# 56_ch_sample-and-hold_card_v1_1.net
KiCad netlist of a schematic drawn in EAGLE
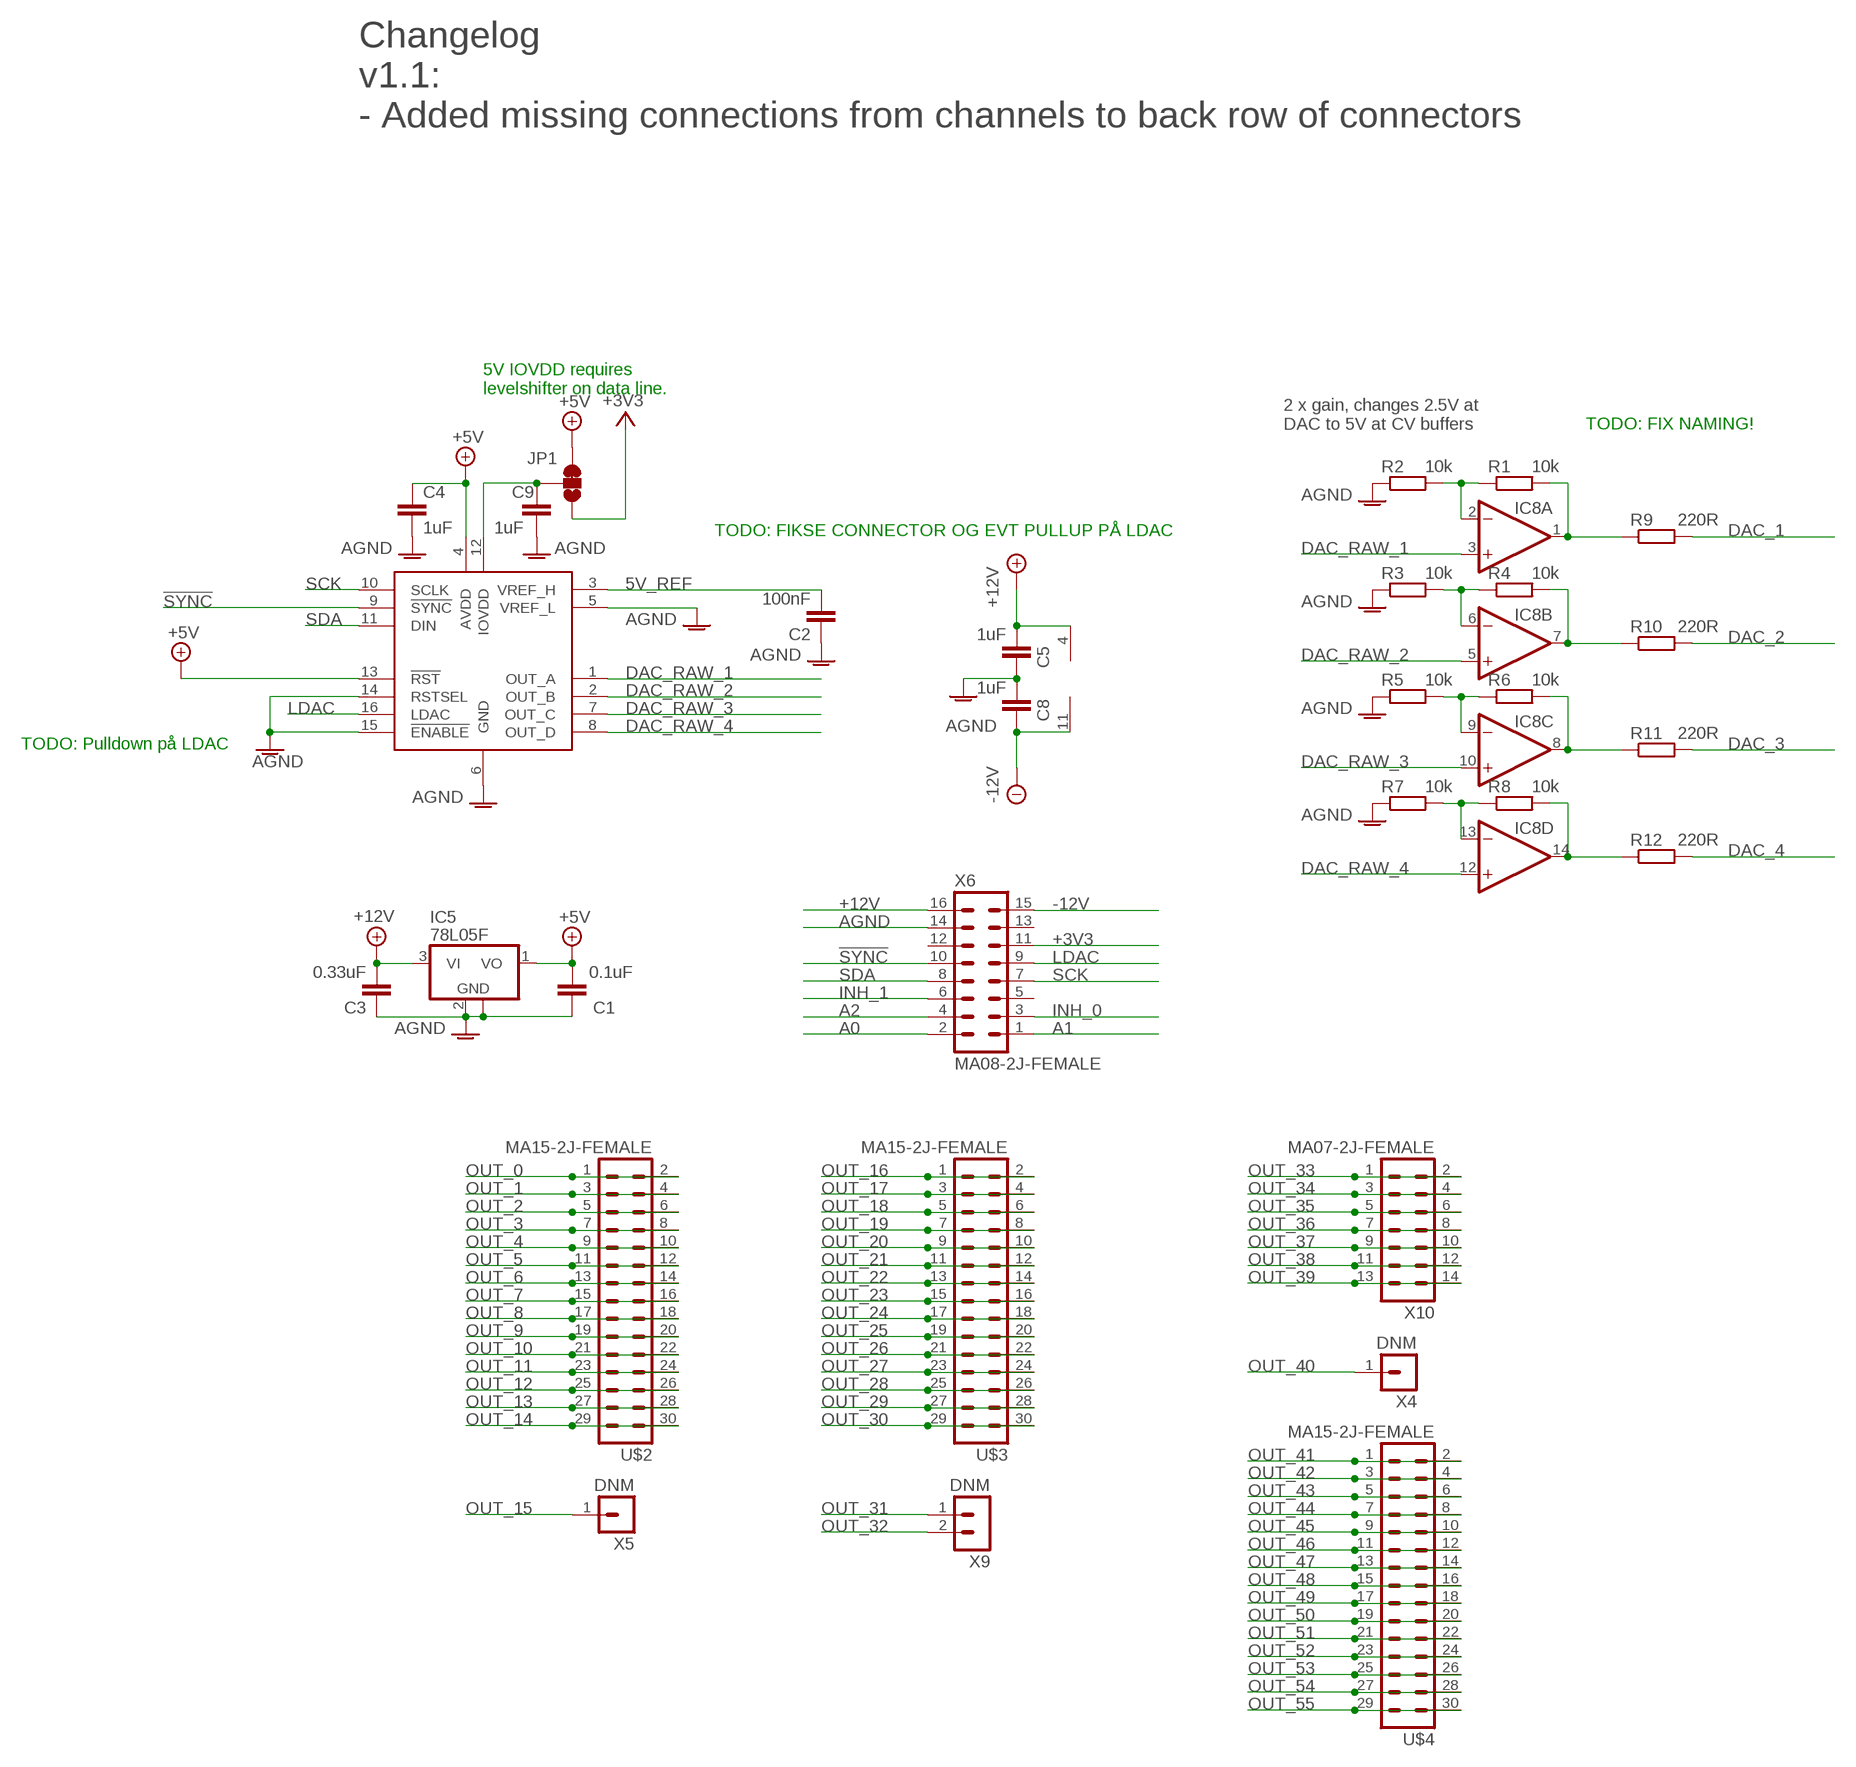
[diagram p0: schematic, sheet 1]
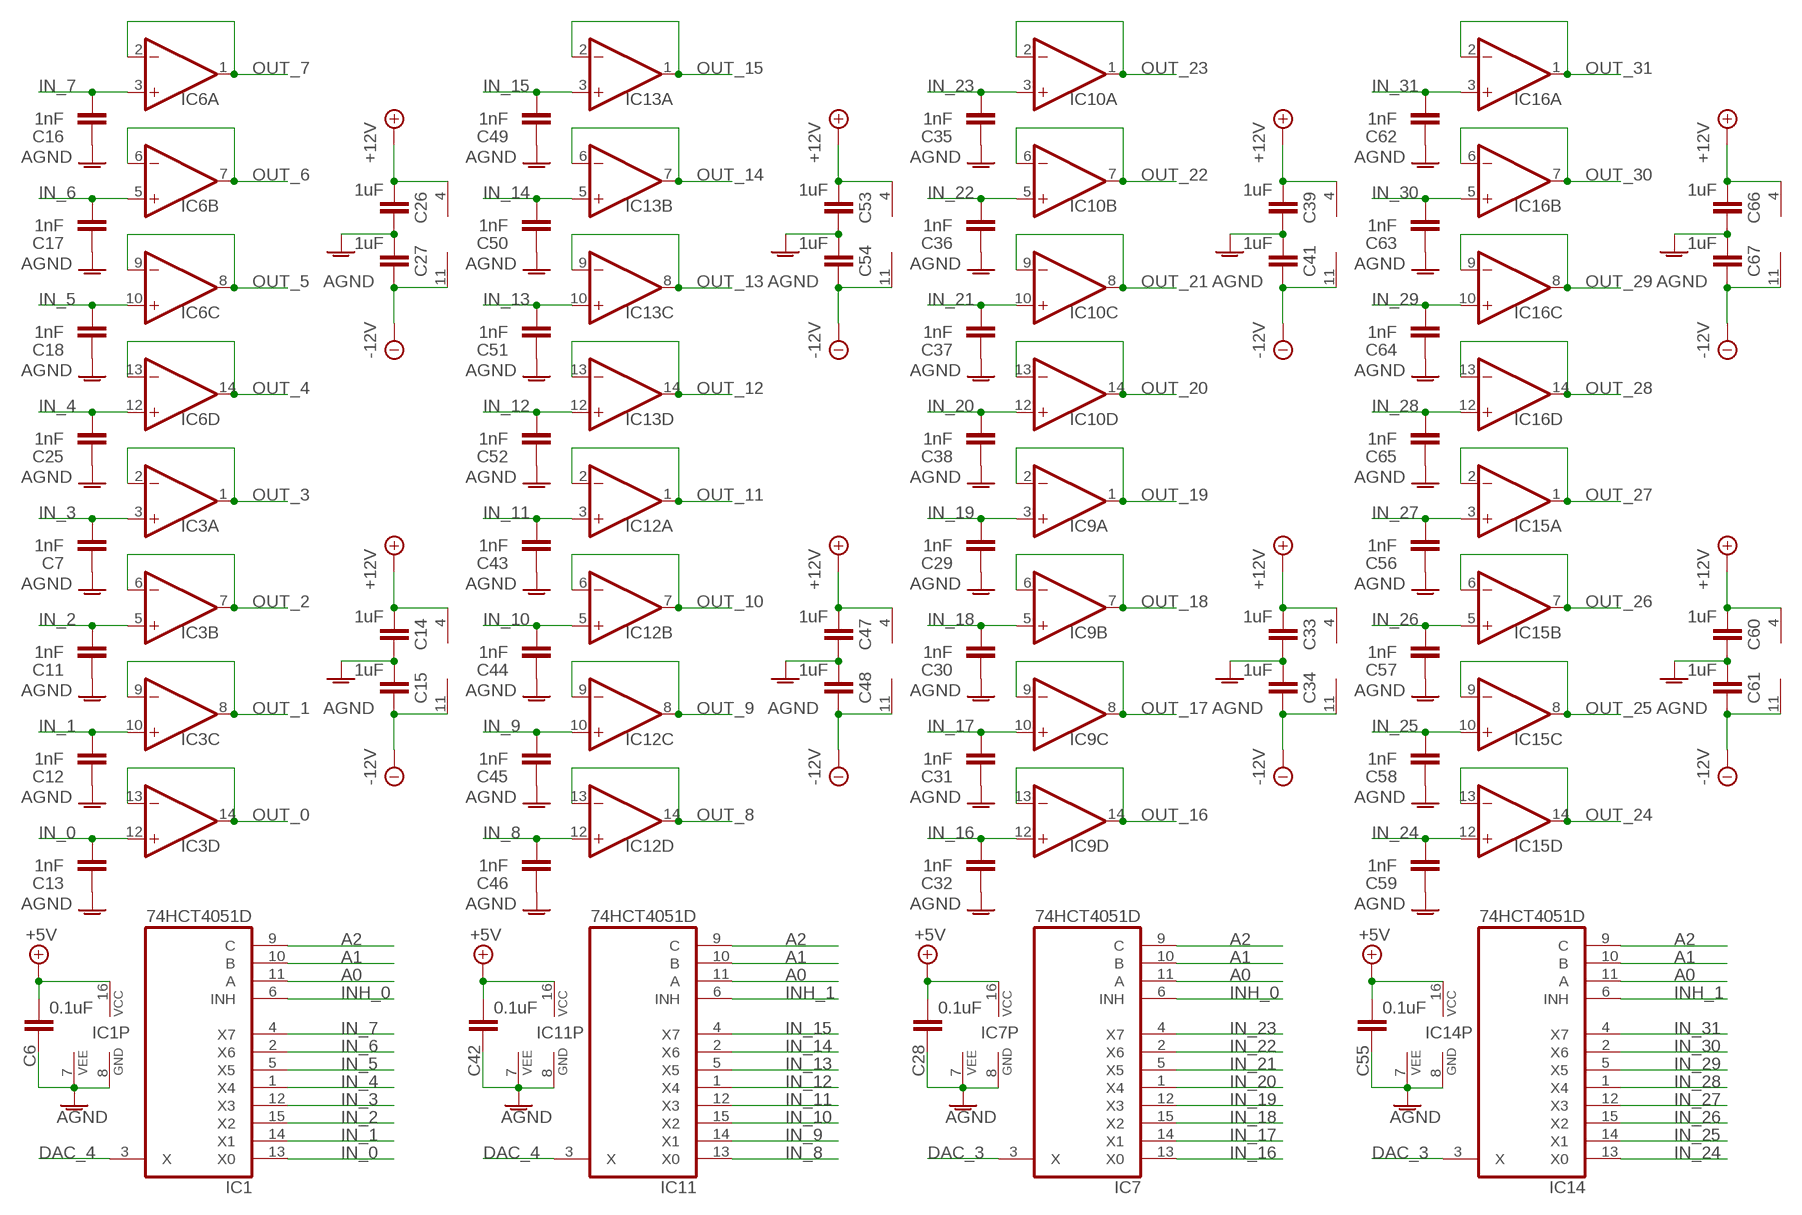
[diagram p1: schematic, sheet 2]
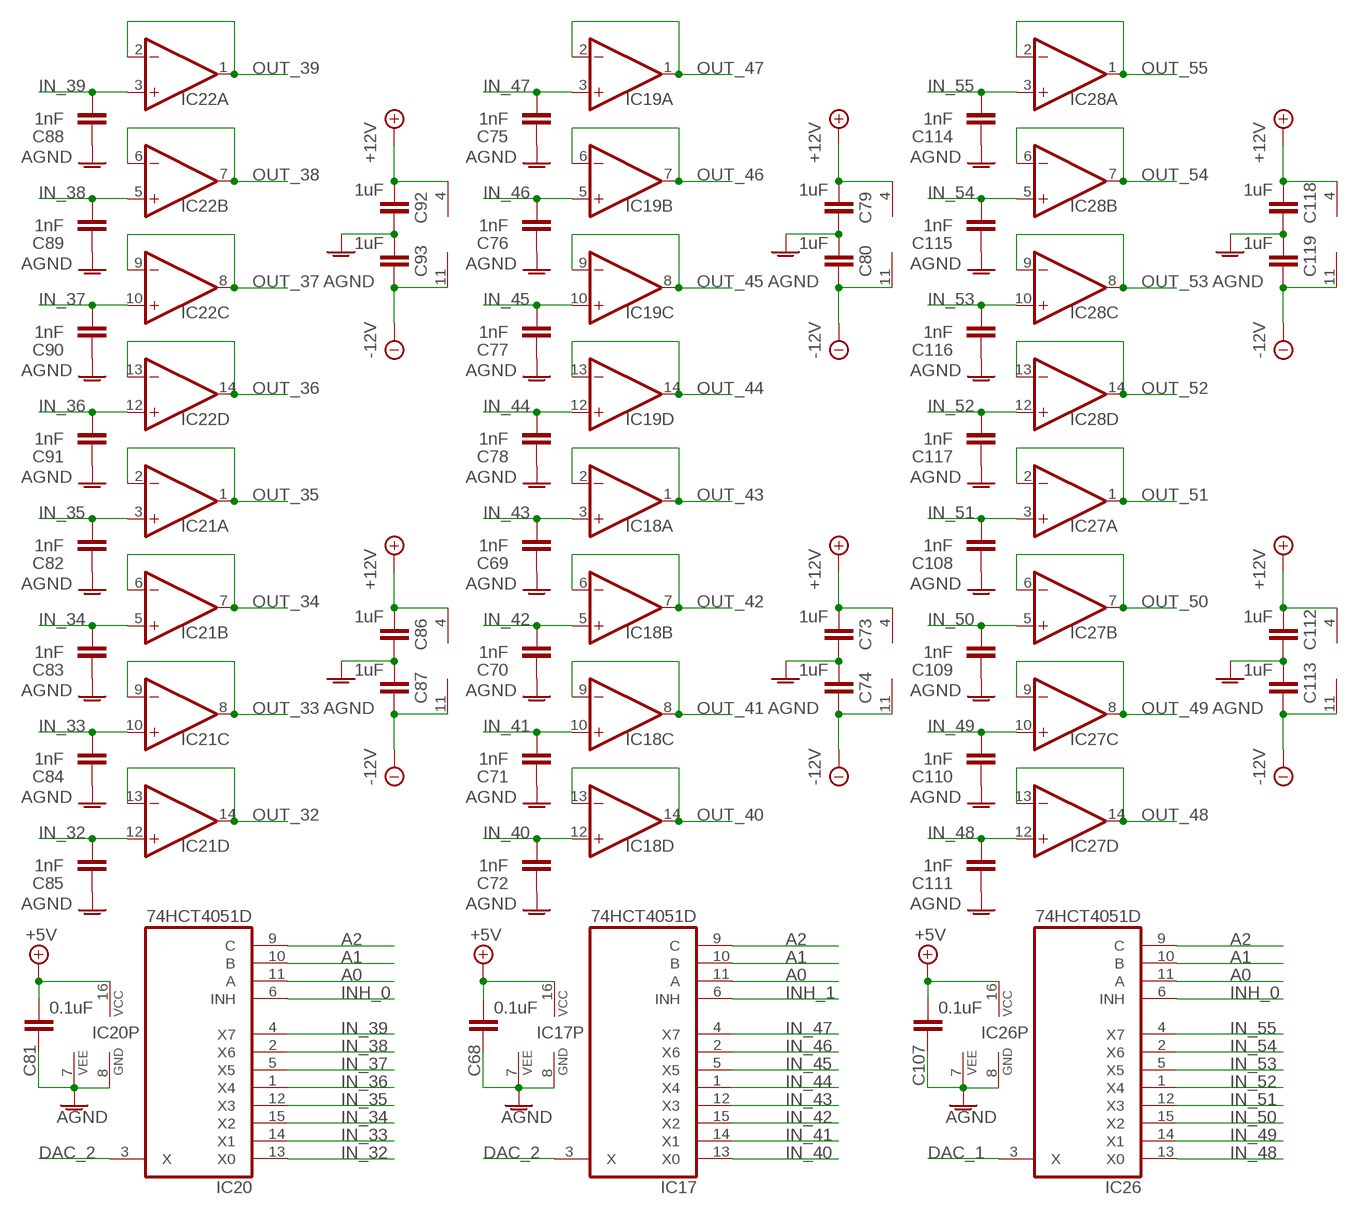
[diagram p2: schematic, sheet 3]

(export (version "E")
  (design (tool "Eeschema 10.0.6"))
  (components
    (comp (ref "C68")
      (value "0.1uF")
      (footprint "eagle-import:C0402-J")
      (libsource (lib "eagle-import") (part "C-EU-J0402"))
    )
    (comp (ref "C69")
      (value "1nF")
      (footprint "eagle-import:C0603-J")
      (libsource (lib "eagle-import") (part "C-EU-J0603"))
    )
    (comp (ref "C70")
      (value "1nF")
      (footprint "eagle-import:C0603-J")
      (libsource (lib "eagle-import") (part "C-EU-J0603"))
    )
    (comp (ref "C71")
      (value "1nF")
      (footprint "eagle-import:C0603-J")
      (libsource (lib "eagle-import") (part "C-EU-J0603"))
    )
    (comp (ref "C72")
      (value "1nF")
      (footprint "eagle-import:C0603-J")
      (libsource (lib "eagle-import") (part "C-EU-J0603"))
    )
    (comp (ref "C73")
      (value "1uF")
      (footprint "eagle-import:C0402-J")
      (libsource (lib "eagle-import") (part "C-EU-J0402"))
    )
    (comp (ref "C74")
      (value "1uF")
      (footprint "eagle-import:C0402-J")
      (libsource (lib "eagle-import") (part "C-EU-J0402"))
    )
    (comp (ref "C75")
      (value "1nF")
      (footprint "eagle-import:C0603-J")
      (libsource (lib "eagle-import") (part "C-EU-J0603"))
    )
    (comp (ref "C76")
      (value "1nF")
      (footprint "eagle-import:C0603-J")
      (libsource (lib "eagle-import") (part "C-EU-J0603"))
    )
    (comp (ref "C77")
      (value "1nF")
      (footprint "eagle-import:C0603-J")
      (libsource (lib "eagle-import") (part "C-EU-J0603"))
    )
    (comp (ref "C78")
      (value "1nF")
      (footprint "eagle-import:C0603-J")
      (libsource (lib "eagle-import") (part "C-EU-J0603"))
    )
    (comp (ref "C79")
      (value "1uF")
      (footprint "eagle-import:C0402-J")
      (libsource (lib "eagle-import") (part "C-EU-J0402"))
    )
    (comp (ref "C80")
      (value "1uF")
      (footprint "eagle-import:C0402-J")
      (libsource (lib "eagle-import") (part "C-EU-J0402"))
    )
    (comp (ref "C81")
      (value "0.1uF")
      (footprint "eagle-import:C0402-J")
      (libsource (lib "eagle-import") (part "C-EU-J0402"))
    )
    (comp (ref "C82")
      (value "1nF")
      (footprint "eagle-import:C0603-J")
      (libsource (lib "eagle-import") (part "C-EU-J0603"))
    )
    (comp (ref "C83")
      (value "1nF")
      (footprint "eagle-import:C0603-J")
      (libsource (lib "eagle-import") (part "C-EU-J0603"))
    )
    (comp (ref "C84")
      (value "1nF")
      (footprint "eagle-import:C0603-J")
      (libsource (lib "eagle-import") (part "C-EU-J0603"))
    )
    (comp (ref "C85")
      (value "1nF")
      (footprint "eagle-import:C0603-J")
      (libsource (lib "eagle-import") (part "C-EU-J0603"))
    )
    (comp (ref "C86")
      (value "1uF")
      (footprint "eagle-import:C0402-J")
      (libsource (lib "eagle-import") (part "C-EU-J0402"))
    )
    (comp (ref "C87")
      (value "1uF")
      (footprint "eagle-import:C0402-J")
      (libsource (lib "eagle-import") (part "C-EU-J0402"))
    )
    (comp (ref "C88")
      (value "1nF")
      (footprint "eagle-import:C0603-J")
      (libsource (lib "eagle-import") (part "C-EU-J0603"))
    )
    (comp (ref "C89")
      (value "1nF")
      (footprint "eagle-import:C0603-J")
      (libsource (lib "eagle-import") (part "C-EU-J0603"))
    )
    (comp (ref "C90")
      (value "1nF")
      (footprint "eagle-import:C0603-J")
      (libsource (lib "eagle-import") (part "C-EU-J0603"))
    )
    (comp (ref "C91")
      (value "1nF")
      (footprint "eagle-import:C0603-J")
      (libsource (lib "eagle-import") (part "C-EU-J0603"))
    )
    (comp (ref "C92")
      (value "1uF")
      (footprint "eagle-import:C0402-J")
      (libsource (lib "eagle-import") (part "C-EU-J0402"))
    )
    (comp (ref "C93")
      (value "1uF")
      (footprint "eagle-import:C0402-J")
      (libsource (lib "eagle-import") (part "C-EU-J0402"))
    )
    (comp (ref "C107")
      (value "0.1uF")
      (footprint "eagle-import:C0402-J")
      (libsource (lib "eagle-import") (part "C-EU-J0402"))
    )
    (comp (ref "C108")
      (value "1nF")
      (footprint "eagle-import:C0603-J")
      (libsource (lib "eagle-import") (part "C-EU-J0603"))
    )
    (comp (ref "C109")
      (value "1nF")
      (footprint "eagle-import:C0603-J")
      (libsource (lib "eagle-import") (part "C-EU-J0603"))
    )
    (comp (ref "C110")
      (value "1nF")
      (footprint "eagle-import:C0603-J")
      (libsource (lib "eagle-import") (part "C-EU-J0603"))
    )
    (comp (ref "C111")
      (value "1nF")
      (footprint "eagle-import:C0603-J")
      (libsource (lib "eagle-import") (part "C-EU-J0603"))
    )
    (comp (ref "C112")
      (value "1uF")
      (footprint "eagle-import:C0402-J")
      (libsource (lib "eagle-import") (part "C-EU-J0402"))
    )
    (comp (ref "C113")
      (value "1uF")
      (footprint "eagle-import:C0402-J")
      (libsource (lib "eagle-import") (part "C-EU-J0402"))
    )
    (comp (ref "C114")
      (value "1nF")
      (footprint "eagle-import:C0603-J")
      (libsource (lib "eagle-import") (part "C-EU-J0603"))
    )
    (comp (ref "C115")
      (value "1nF")
      (footprint "eagle-import:C0603-J")
      (libsource (lib "eagle-import") (part "C-EU-J0603"))
    )
    (comp (ref "C116")
      (value "1nF")
      (footprint "eagle-import:C0603-J")
      (libsource (lib "eagle-import") (part "C-EU-J0603"))
    )
    (comp (ref "C117")
      (value "1nF")
      (footprint "eagle-import:C0603-J")
      (libsource (lib "eagle-import") (part "C-EU-J0603"))
    )
    (comp (ref "C118")
      (value "1uF")
      (footprint "eagle-import:C0402-J")
      (libsource (lib "eagle-import") (part "C-EU-J0402"))
    )
    (comp (ref "C119")
      (value "1uF")
      (footprint "eagle-import:C0402-J")
      (libsource (lib "eagle-import") (part "C-EU-J0402"))
    )
    (comp (ref "IC17")
      (value "74HCT4051D")
      (footprint "eagle-import:SO16")
      (libsource (lib "eagle-import") (part "4051D"))
    )
    (comp (ref "IC18")
      (value "TL074JT")
      (footprint "eagle-import:TSSOP14J")
      (libsource (lib "eagle-import") (part "TL074JT"))
    )
    (comp (ref "IC19")
      (value "TL074JT")
      (footprint "eagle-import:TSSOP14J")
      (libsource (lib "eagle-import") (part "TL074JT"))
    )
    (comp (ref "IC20")
      (value "74HCT4051D")
      (footprint "eagle-import:SO16")
      (libsource (lib "eagle-import") (part "4051D"))
    )
    (comp (ref "IC21")
      (value "TL074JT")
      (footprint "eagle-import:TSSOP14J")
      (libsource (lib "eagle-import") (part "TL074JT"))
    )
    (comp (ref "IC22")
      (value "TL074JT")
      (footprint "eagle-import:TSSOP14J")
      (libsource (lib "eagle-import") (part "TL074JT"))
    )
    (comp (ref "IC26")
      (value "74HCT4051D")
      (footprint "eagle-import:SO16")
      (libsource (lib "eagle-import") (part "4051D"))
    )
    (comp (ref "IC27")
      (value "TL074JT")
      (footprint "eagle-import:TSSOP14J")
      (libsource (lib "eagle-import") (part "TL074JT"))
    )
    (comp (ref "IC28")
      (value "TL074JT")
      (footprint "eagle-import:TSSOP14J")
      (libsource (lib "eagle-import") (part "TL074JT"))
    )
    (comp (ref "C1")
      (value "0.1uF")
      (footprint "eagle-import:C0603")
      (libsource (lib "eagle-import") (part "C-EUC0603"))
    )
    (comp (ref "C2")
      (value "100nF")
      (footprint "eagle-import:C0603")
      (libsource (lib "eagle-import") (part "C-EUC0603"))
    )
    (comp (ref "C3")
      (value "0.33uF")
      (footprint "eagle-import:C0603")
      (libsource (lib "eagle-import") (part "C-EUC0603"))
    )
    (comp (ref "C4")
      (value "1uF")
      (footprint "eagle-import:C0402-J")
      (libsource (lib "eagle-import") (part "C-EU-J0402"))
    )
    (comp (ref "C5")
      (value "1uF")
      (footprint "eagle-import:C0402-J")
      (libsource (lib "eagle-import") (part "C-EU-J0402"))
    )
    (comp (ref "C8")
      (value "1uF")
      (footprint "eagle-import:C0402-J")
      (libsource (lib "eagle-import") (part "C-EU-J0402"))
    )
    (comp (ref "C9")
      (value "1uF")
      (footprint "eagle-import:C0402-J")
      (libsource (lib "eagle-import") (part "C-EU-J0402"))
    )
    (comp (ref "IC2")
      (value "DAC8565F")
      (footprint "eagle-import:DIL16-FM-CON")
      (libsource (lib "eagle-import") (part "DAC8565F"))
    )
    (comp (ref "IC5")
      (value "78L05F")
      (footprint "eagle-import:SOT89")
      (libsource (lib "eagle-import") (part "78LF05"))
    )
    (comp (ref "IC8")
      (value "TL074JT")
      (footprint "eagle-import:TSSOP14J")
      (libsource (lib "eagle-import") (part "TL074JT"))
    )
    (comp (ref "JP1")
      (value "JUMPER-SMT_3_1-NC_TRACE_NO-SILK_DNM")
      (footprint "eagle-import:SMT-JUMPER_3_1-NC_TRACE_NO-SILK")
      (libsource (lib "eagle-import") (part "JUMPER-SMT_3_1-NC_TRACE_NO-SILK"))
    )
    (comp (ref "R1")
      (value "10k")
      (footprint "eagle-import:R0603")
      (libsource (lib "eagle-import") (part "R-EU_R0603"))
    )
    (comp (ref "R2")
      (value "10k")
      (footprint "eagle-import:R0603")
      (libsource (lib "eagle-import") (part "R-EU_R0603"))
    )
    (comp (ref "R3")
      (value "10k")
      (footprint "eagle-import:R0603")
      (libsource (lib "eagle-import") (part "R-EU_R0603"))
    )
    (comp (ref "R4")
      (value "10k")
      (footprint "eagle-import:R0603")
      (libsource (lib "eagle-import") (part "R-EU_R0603"))
    )
    (comp (ref "R5")
      (value "10k")
      (footprint "eagle-import:R0603")
      (libsource (lib "eagle-import") (part "R-EU_R0603"))
    )
    (comp (ref "R6")
      (value "10k")
      (footprint "eagle-import:R0603")
      (libsource (lib "eagle-import") (part "R-EU_R0603"))
    )
    (comp (ref "R7")
      (value "10k")
      (footprint "eagle-import:R0603")
      (libsource (lib "eagle-import") (part "R-EU_R0603"))
    )
    (comp (ref "R8")
      (value "10k")
      (footprint "eagle-import:R0603")
      (libsource (lib "eagle-import") (part "R-EU_R0603"))
    )
    (comp (ref "R9")
      (value "220R")
      (footprint "eagle-import:R0603")
      (libsource (lib "eagle-import") (part "R-EU_R0603"))
    )
    (comp (ref "R10")
      (value "220R")
      (footprint "eagle-import:R0603")
      (libsource (lib "eagle-import") (part "R-EU_R0603"))
    )
    (comp (ref "R11")
      (value "220R")
      (footprint "eagle-import:R0603")
      (libsource (lib "eagle-import") (part "R-EU_R0603"))
    )
    (comp (ref "R12")
      (value "220R")
      (footprint "eagle-import:R0603")
      (libsource (lib "eagle-import") (part "R-EU_R0603"))
    )
    (comp (ref "U$2")
      (value "MA15-2J-FEMALE")
      (footprint "eagle-import:MA15-2J")
      (libsource (lib "eagle-import") (part "MA15-2J"))
    )
    (comp (ref "U$3")
      (value "MA15-2J-FEMALE")
      (footprint "eagle-import:MA15-2J")
      (libsource (lib "eagle-import") (part "MA15-2J"))
    )
    (comp (ref "U$4")
      (value "MA15-2J-FEMALE")
      (footprint "eagle-import:MA15-2J")
      (libsource (lib "eagle-import") (part "MA15-2J"))
    )
    (comp (ref "X4")
      (value "DNM")
      (footprint "eagle-import:MA01N-1J")
      (libsource (lib "eagle-import") (part "MA01-1JN"))
    )
    (comp (ref "X5")
      (value "DNM")
      (footprint "eagle-import:MA01N-1J")
      (libsource (lib "eagle-import") (part "MA01-1JN"))
    )
    (comp (ref "X6")
      (value "MA08-2J-FEMALE")
      (footprint "eagle-import:MA08-2J")
      (libsource (lib "eagle-import") (part "MA08-2J"))
    )
    (comp (ref "X9")
      (value "DNM")
      (footprint "eagle-import:MA02N-1J")
      (libsource (lib "eagle-import") (part "MA02-1JN"))
    )
    (comp (ref "X10")
      (value "MA07-2J-FEMALE")
      (footprint "eagle-import:MA07-2J")
      (libsource (lib "eagle-import") (part "MA07-2J"))
    )
    (comp (ref "C6")
      (value "0.1uF")
      (footprint "eagle-import:C0402-J")
      (libsource (lib "eagle-import") (part "C-EU-J0402"))
    )
    (comp (ref "C7")
      (value "1nF")
      (footprint "eagle-import:C0603-J")
      (libsource (lib "eagle-import") (part "C-EU-J0603"))
    )
    (comp (ref "C11")
      (value "1nF")
      (footprint "eagle-import:C0603-J")
      (libsource (lib "eagle-import") (part "C-EU-J0603"))
    )
    (comp (ref "C12")
      (value "1nF")
      (footprint "eagle-import:C0603-J")
      (libsource (lib "eagle-import") (part "C-EU-J0603"))
    )
    (comp (ref "C13")
      (value "1nF")
      (footprint "eagle-import:C0603-J")
      (libsource (lib "eagle-import") (part "C-EU-J0603"))
    )
    (comp (ref "C14")
      (value "1uF")
      (footprint "eagle-import:C0402-J")
      (libsource (lib "eagle-import") (part "C-EU-J0402"))
    )
    (comp (ref "C15")
      (value "1uF")
      (footprint "eagle-import:C0402-J")
      (libsource (lib "eagle-import") (part "C-EU-J0402"))
    )
    (comp (ref "C16")
      (value "1nF")
      (footprint "eagle-import:C0603-J")
      (libsource (lib "eagle-import") (part "C-EU-J0603"))
    )
    (comp (ref "C17")
      (value "1nF")
      (footprint "eagle-import:C0603-J")
      (libsource (lib "eagle-import") (part "C-EU-J0603"))
    )
    (comp (ref "C18")
      (value "1nF")
      (footprint "eagle-import:C0603-J")
      (libsource (lib "eagle-import") (part "C-EU-J0603"))
    )
    (comp (ref "C25")
      (value "1nF")
      (footprint "eagle-import:C0603-J")
      (libsource (lib "eagle-import") (part "C-EU-J0603"))
    )
    (comp (ref "C26")
      (value "1uF")
      (footprint "eagle-import:C0402-J")
      (libsource (lib "eagle-import") (part "C-EU-J0402"))
    )
    (comp (ref "C27")
      (value "1uF")
      (footprint "eagle-import:C0402-J")
      (libsource (lib "eagle-import") (part "C-EU-J0402"))
    )
    (comp (ref "C28")
      (value "0.1uF")
      (footprint "eagle-import:C0402-J")
      (libsource (lib "eagle-import") (part "C-EU-J0402"))
    )
    (comp (ref "C29")
      (value "1nF")
      (footprint "eagle-import:C0603-J")
      (libsource (lib "eagle-import") (part "C-EU-J0603"))
    )
    (comp (ref "C30")
      (value "1nF")
      (footprint "eagle-import:C0603-J")
      (libsource (lib "eagle-import") (part "C-EU-J0603"))
    )
    (comp (ref "C31")
      (value "1nF")
      (footprint "eagle-import:C0603-J")
      (libsource (lib "eagle-import") (part "C-EU-J0603"))
    )
    (comp (ref "C32")
      (value "1nF")
      (footprint "eagle-import:C0603-J")
      (libsource (lib "eagle-import") (part "C-EU-J0603"))
    )
    (comp (ref "C33")
      (value "1uF")
      (footprint "eagle-import:C0402-J")
      (libsource (lib "eagle-import") (part "C-EU-J0402"))
    )
    (comp (ref "C34")
      (value "1uF")
      (footprint "eagle-import:C0402-J")
      (libsource (lib "eagle-import") (part "C-EU-J0402"))
    )
    (comp (ref "C35")
      (value "1nF")
      (footprint "eagle-import:C0603-J")
      (libsource (lib "eagle-import") (part "C-EU-J0603"))
    )
    (comp (ref "C36")
      (value "1nF")
      (footprint "eagle-import:C0603-J")
      (libsource (lib "eagle-import") (part "C-EU-J0603"))
    )
    (comp (ref "C37")
      (value "1nF")
      (footprint "eagle-import:C0603-J")
      (libsource (lib "eagle-import") (part "C-EU-J0603"))
    )
    (comp (ref "C38")
      (value "1nF")
      (footprint "eagle-import:C0603-J")
      (libsource (lib "eagle-import") (part "C-EU-J0603"))
    )
    (comp (ref "C39")
      (value "1uF")
      (footprint "eagle-import:C0402-J")
      (libsource (lib "eagle-import") (part "C-EU-J0402"))
    )
    (comp (ref "C41")
      (value "1uF")
      (footprint "eagle-import:C0402-J")
      (libsource (lib "eagle-import") (part "C-EU-J0402"))
    )
    (comp (ref "C42")
      (value "0.1uF")
      (footprint "eagle-import:C0402-J")
      (libsource (lib "eagle-import") (part "C-EU-J0402"))
    )
    (comp (ref "C43")
      (value "1nF")
      (footprint "eagle-import:C0603-J")
      (libsource (lib "eagle-import") (part "C-EU-J0603"))
    )
    (comp (ref "C44")
      (value "1nF")
      (footprint "eagle-import:C0603-J")
      (libsource (lib "eagle-import") (part "C-EU-J0603"))
    )
    (comp (ref "C45")
      (value "1nF")
      (footprint "eagle-import:C0603-J")
      (libsource (lib "eagle-import") (part "C-EU-J0603"))
    )
    (comp (ref "C46")
      (value "1nF")
      (footprint "eagle-import:C0603-J")
      (libsource (lib "eagle-import") (part "C-EU-J0603"))
    )
    (comp (ref "C47")
      (value "1uF")
      (footprint "eagle-import:C0402-J")
      (libsource (lib "eagle-import") (part "C-EU-J0402"))
    )
    (comp (ref "C48")
      (value "1uF")
      (footprint "eagle-import:C0402-J")
      (libsource (lib "eagle-import") (part "C-EU-J0402"))
    )
    (comp (ref "C49")
      (value "1nF")
      (footprint "eagle-import:C0603-J")
      (libsource (lib "eagle-import") (part "C-EU-J0603"))
    )
    (comp (ref "C50")
      (value "1nF")
      (footprint "eagle-import:C0603-J")
      (libsource (lib "eagle-import") (part "C-EU-J0603"))
    )
    (comp (ref "C51")
      (value "1nF")
      (footprint "eagle-import:C0603-J")
      (libsource (lib "eagle-import") (part "C-EU-J0603"))
    )
    (comp (ref "C52")
      (value "1nF")
      (footprint "eagle-import:C0603-J")
      (libsource (lib "eagle-import") (part "C-EU-J0603"))
    )
    (comp (ref "C53")
      (value "1uF")
      (footprint "eagle-import:C0402-J")
      (libsource (lib "eagle-import") (part "C-EU-J0402"))
    )
    (comp (ref "C54")
      (value "1uF")
      (footprint "eagle-import:C0402-J")
      (libsource (lib "eagle-import") (part "C-EU-J0402"))
    )
    (comp (ref "C55")
      (value "0.1uF")
      (footprint "eagle-import:C0402-J")
      (libsource (lib "eagle-import") (part "C-EU-J0402"))
    )
    (comp (ref "C56")
      (value "1nF")
      (footprint "eagle-import:C0603-J")
      (libsource (lib "eagle-import") (part "C-EU-J0603"))
    )
    (comp (ref "C57")
      (value "1nF")
      (footprint "eagle-import:C0603-J")
      (libsource (lib "eagle-import") (part "C-EU-J0603"))
    )
    (comp (ref "C58")
      (value "1nF")
      (footprint "eagle-import:C0603-J")
      (libsource (lib "eagle-import") (part "C-EU-J0603"))
    )
    (comp (ref "C59")
      (value "1nF")
      (footprint "eagle-import:C0603-J")
      (libsource (lib "eagle-import") (part "C-EU-J0603"))
    )
    (comp (ref "C60")
      (value "1uF")
      (footprint "eagle-import:C0402-J")
      (libsource (lib "eagle-import") (part "C-EU-J0402"))
    )
    (comp (ref "C61")
      (value "1uF")
      (footprint "eagle-import:C0402-J")
      (libsource (lib "eagle-import") (part "C-EU-J0402"))
    )
    (comp (ref "C62")
      (value "1nF")
      (footprint "eagle-import:C0603-J")
      (libsource (lib "eagle-import") (part "C-EU-J0603"))
    )
    (comp (ref "C63")
      (value "1nF")
      (footprint "eagle-import:C0603-J")
      (libsource (lib "eagle-import") (part "C-EU-J0603"))
    )
    (comp (ref "C64")
      (value "1nF")
      (footprint "eagle-import:C0603-J")
      (libsource (lib "eagle-import") (part "C-EU-J0603"))
    )
    (comp (ref "C65")
      (value "1nF")
      (footprint "eagle-import:C0603-J")
      (libsource (lib "eagle-import") (part "C-EU-J0603"))
    )
    (comp (ref "C66")
      (value "1uF")
      (footprint "eagle-import:C0402-J")
      (libsource (lib "eagle-import") (part "C-EU-J0402"))
    )
    (comp (ref "C67")
      (value "1uF")
      (footprint "eagle-import:C0402-J")
      (libsource (lib "eagle-import") (part "C-EU-J0402"))
    )
    (comp (ref "IC1")
      (value "74HCT4051D")
      (footprint "eagle-import:SO16")
      (libsource (lib "eagle-import") (part "4051D"))
    )
    (comp (ref "IC3")
      (value "TL074JT")
      (footprint "eagle-import:TSSOP14J")
      (libsource (lib "eagle-import") (part "TL074JT"))
    )
    (comp (ref "IC6")
      (value "TL074JT")
      (footprint "eagle-import:TSSOP14J")
      (libsource (lib "eagle-import") (part "TL074JT"))
    )
    (comp (ref "IC7")
      (value "74HCT4051D")
      (footprint "eagle-import:SO16")
      (libsource (lib "eagle-import") (part "4051D"))
    )
    (comp (ref "IC9")
      (value "TL074JT")
      (footprint "eagle-import:TSSOP14J")
      (libsource (lib "eagle-import") (part "TL074JT"))
    )
    (comp (ref "IC10")
      (value "TL074JT")
      (footprint "eagle-import:TSSOP14J")
      (libsource (lib "eagle-import") (part "TL074JT"))
    )
    (comp (ref "IC11")
      (value "74HCT4051D")
      (footprint "eagle-import:SO16")
      (libsource (lib "eagle-import") (part "4051D"))
    )
    (comp (ref "IC12")
      (value "TL074JT")
      (footprint "eagle-import:TSSOP14J")
      (libsource (lib "eagle-import") (part "TL074JT"))
    )
    (comp (ref "IC13")
      (value "TL074JT")
      (footprint "eagle-import:TSSOP14J")
      (libsource (lib "eagle-import") (part "TL074JT"))
    )
    (comp (ref "IC14")
      (value "74HCT4051D")
      (footprint "eagle-import:SO16")
      (libsource (lib "eagle-import") (part "4051D"))
    )
    (comp (ref "IC15")
      (value "TL074JT")
      (footprint "eagle-import:TSSOP14J")
      (libsource (lib "eagle-import") (part "TL074JT"))
    )
    (comp (ref "IC16")
      (value "TL074JT")
      (footprint "eagle-import:TSSOP14J")
      (libsource (lib "eagle-import") (part "TL074JT"))
    )
  )
  (nets
    (net (code "1") (name "+3V3") (class "Default")
      (node (ref "JP1") (pin "1") (pinfunction "1_1") (pintype "passive"))
      (node (ref "X6") (pin "11") (pinfunction "11_11") (pintype "passive"))
    )
    (net (code "2") (name "+5V") (class "Default")
      (node (ref "C1") (pin "2") (pinfunction "2_2") (pintype "passive"))
      (node (ref "C107") (pin "2") (pinfunction "2_2") (pintype "passive"))
      (node (ref "C28") (pin "2") (pinfunction "2_2") (pintype "passive"))
      (node (ref "C4") (pin "1") (pinfunction "1_1") (pintype "passive"))
      (node (ref "C42") (pin "2") (pinfunction "2_2") (pintype "passive"))
      (node (ref "C55") (pin "2") (pinfunction "2_2") (pintype "passive"))
      (node (ref "C6") (pin "2") (pinfunction "2_2") (pintype "passive"))
      (node (ref "C68") (pin "2") (pinfunction "2_2") (pintype "passive"))
      (node (ref "C81") (pin "2") (pinfunction "2_2") (pintype "passive"))
      (node (ref "IC1") (pin "16") (pinfunction "VCC_16") (pintype "power_in"))
      (node (ref "IC11") (pin "16") (pinfunction "VCC_16") (pintype "power_in"))
      (node (ref "IC14") (pin "16") (pinfunction "VCC_16") (pintype "power_in"))
      (node (ref "IC17") (pin "16") (pinfunction "VCC_16") (pintype "power_in"))
      (node (ref "IC2") (pin "13") (pinfunction "~{RST}_13") (pintype "bidirectional"))
      (node (ref "IC2") (pin "4") (pinfunction "AVDD_4") (pintype "power_in"))
      (node (ref "IC20") (pin "16") (pinfunction "VCC_16") (pintype "power_in"))
      (node (ref "IC26") (pin "16") (pinfunction "VCC_16") (pintype "power_in"))
      (node (ref "IC5") (pin "1") (pinfunction "VO_1") (pintype "passive"))
      (node (ref "IC7") (pin "16") (pinfunction "VCC_16") (pintype "power_in"))
      (node (ref "JP1") (pin "3") (pinfunction "3_3") (pintype "passive"))
    )
    (net (code "3") (name "+12V") (class "Default")
      (node (ref "C112") (pin "1") (pinfunction "1_1") (pintype "passive"))
      (node (ref "C118") (pin "1") (pinfunction "1_1") (pintype "passive"))
      (node (ref "C14") (pin "1") (pinfunction "1_1") (pintype "passive"))
      (node (ref "C26") (pin "1") (pinfunction "1_1") (pintype "passive"))
      (node (ref "C3") (pin "2") (pinfunction "2_2") (pintype "passive"))
      (node (ref "C33") (pin "1") (pinfunction "1_1") (pintype "passive"))
      (node (ref "C39") (pin "1") (pinfunction "1_1") (pintype "passive"))
      (node (ref "C47") (pin "1") (pinfunction "1_1") (pintype "passive"))
      (node (ref "C5") (pin "1") (pinfunction "1_1") (pintype "passive"))
      (node (ref "C53") (pin "1") (pinfunction "1_1") (pintype "passive"))
      (node (ref "C60") (pin "1") (pinfunction "1_1") (pintype "passive"))
      (node (ref "C66") (pin "1") (pinfunction "1_1") (pintype "passive"))
      (node (ref "C73") (pin "1") (pinfunction "1_1") (pintype "passive"))
      (node (ref "C79") (pin "1") (pinfunction "1_1") (pintype "passive"))
      (node (ref "C86") (pin "1") (pinfunction "1_1") (pintype "passive"))
      (node (ref "C92") (pin "1") (pinfunction "1_1") (pintype "passive"))
      (node (ref "IC10") (pin "4") (pinfunction "V+_4") (pintype "power_in"))
      (node (ref "IC12") (pin "4") (pinfunction "V+_4") (pintype "power_in"))
      (node (ref "IC13") (pin "4") (pinfunction "V+_4") (pintype "power_in"))
      (node (ref "IC15") (pin "4") (pinfunction "V+_4") (pintype "power_in"))
      (node (ref "IC16") (pin "4") (pinfunction "V+_4") (pintype "power_in"))
      (node (ref "IC18") (pin "4") (pinfunction "V+_4") (pintype "power_in"))
      (node (ref "IC19") (pin "4") (pinfunction "V+_4") (pintype "power_in"))
      (node (ref "IC21") (pin "4") (pinfunction "V+_4") (pintype "power_in"))
      (node (ref "IC22") (pin "4") (pinfunction "V+_4") (pintype "power_in"))
      (node (ref "IC27") (pin "4") (pinfunction "V+_4") (pintype "power_in"))
      (node (ref "IC28") (pin "4") (pinfunction "V+_4") (pintype "power_in"))
      (node (ref "IC3") (pin "4") (pinfunction "V+_4") (pintype "power_in"))
      (node (ref "IC5") (pin "3") (pinfunction "VI_3") (pintype "input"))
      (node (ref "IC6") (pin "4") (pinfunction "V+_4") (pintype "power_in"))
      (node (ref "IC8") (pin "4") (pinfunction "V+_4") (pintype "power_in"))
      (node (ref "IC9") (pin "4") (pinfunction "V+_4") (pintype "power_in"))
      (node (ref "X6") (pin "16") (pinfunction "16_16") (pintype "passive"))
    )
    (net (code "4") (name "-12V") (class "Default")
      (node (ref "C113") (pin "2") (pinfunction "2_2") (pintype "passive"))
      (node (ref "C119") (pin "2") (pinfunction "2_2") (pintype "passive"))
      (node (ref "C15") (pin "2") (pinfunction "2_2") (pintype "passive"))
      (node (ref "C27") (pin "2") (pinfunction "2_2") (pintype "passive"))
      (node (ref "C34") (pin "2") (pinfunction "2_2") (pintype "passive"))
      (node (ref "C41") (pin "2") (pinfunction "2_2") (pintype "passive"))
      (node (ref "C48") (pin "2") (pinfunction "2_2") (pintype "passive"))
      (node (ref "C54") (pin "2") (pinfunction "2_2") (pintype "passive"))
      (node (ref "C61") (pin "2") (pinfunction "2_2") (pintype "passive"))
      (node (ref "C67") (pin "2") (pinfunction "2_2") (pintype "passive"))
      (node (ref "C74") (pin "2") (pinfunction "2_2") (pintype "passive"))
      (node (ref "C8") (pin "2") (pinfunction "2_2") (pintype "passive"))
      (node (ref "C80") (pin "2") (pinfunction "2_2") (pintype "passive"))
      (node (ref "C87") (pin "2") (pinfunction "2_2") (pintype "passive"))
      (node (ref "C93") (pin "2") (pinfunction "2_2") (pintype "passive"))
      (node (ref "IC10") (pin "11") (pinfunction "V-_11") (pintype "power_in"))
      (node (ref "IC12") (pin "11") (pinfunction "V-_11") (pintype "power_in"))
      (node (ref "IC13") (pin "11") (pinfunction "V-_11") (pintype "power_in"))
      (node (ref "IC15") (pin "11") (pinfunction "V-_11") (pintype "power_in"))
      (node (ref "IC16") (pin "11") (pinfunction "V-_11") (pintype "power_in"))
      (node (ref "IC18") (pin "11") (pinfunction "V-_11") (pintype "power_in"))
      (node (ref "IC19") (pin "11") (pinfunction "V-_11") (pintype "power_in"))
      (node (ref "IC21") (pin "11") (pinfunction "V-_11") (pintype "power_in"))
      (node (ref "IC22") (pin "11") (pinfunction "V-_11") (pintype "power_in"))
      (node (ref "IC27") (pin "11") (pinfunction "V-_11") (pintype "power_in"))
      (node (ref "IC28") (pin "11") (pinfunction "V-_11") (pintype "power_in"))
      (node (ref "IC3") (pin "11") (pinfunction "V-_11") (pintype "power_in"))
      (node (ref "IC6") (pin "11") (pinfunction "V-_11") (pintype "power_in"))
      (node (ref "IC8") (pin "11") (pinfunction "V-_11") (pintype "power_in"))
      (node (ref "IC9") (pin "11") (pinfunction "V-_11") (pintype "power_in"))
      (node (ref "X6") (pin "15") (pinfunction "15_15") (pintype "passive"))
    )
    (net (code "5") (name "5V_REF") (class "Default")
      (node (ref "C2") (pin "2") (pinfunction "2_2") (pintype "passive"))
      (node (ref "IC2") (pin "3") (pinfunction "VREF_H_3") (pintype "bidirectional"))
    )
    (net (code "6") (name "A0") (class "Default")
      (node (ref "IC1") (pin "11") (pinfunction "A_11") (pintype "input"))
      (node (ref "IC11") (pin "11") (pinfunction "A_11") (pintype "input"))
      (node (ref "IC14") (pin "11") (pinfunction "A_11") (pintype "input"))
      (node (ref "IC17") (pin "11") (pinfunction "A_11") (pintype "input"))
      (node (ref "IC20") (pin "11") (pinfunction "A_11") (pintype "input"))
      (node (ref "IC26") (pin "11") (pinfunction "A_11") (pintype "input"))
      (node (ref "IC7") (pin "11") (pinfunction "A_11") (pintype "input"))
      (node (ref "X6") (pin "2") (pinfunction "2_2") (pintype "passive"))
    )
    (net (code "7") (name "A1") (class "Default")
      (node (ref "IC1") (pin "10") (pinfunction "B_10") (pintype "input"))
      (node (ref "IC11") (pin "10") (pinfunction "B_10") (pintype "input"))
      (node (ref "IC14") (pin "10") (pinfunction "B_10") (pintype "input"))
      (node (ref "IC17") (pin "10") (pinfunction "B_10") (pintype "input"))
      (node (ref "IC20") (pin "10") (pinfunction "B_10") (pintype "input"))
      (node (ref "IC26") (pin "10") (pinfunction "B_10") (pintype "input"))
      (node (ref "IC7") (pin "10") (pinfunction "B_10") (pintype "input"))
      (node (ref "X6") (pin "1") (pinfunction "1_1") (pintype "passive"))
    )
    (net (code "8") (name "A2") (class "Default")
      (node (ref "IC1") (pin "9") (pinfunction "C_9") (pintype "input"))
      (node (ref "IC11") (pin "9") (pinfunction "C_9") (pintype "input"))
      (node (ref "IC14") (pin "9") (pinfunction "C_9") (pintype "input"))
      (node (ref "IC17") (pin "9") (pinfunction "C_9") (pintype "input"))
      (node (ref "IC20") (pin "9") (pinfunction "C_9") (pintype "input"))
      (node (ref "IC26") (pin "9") (pinfunction "C_9") (pintype "input"))
      (node (ref "IC7") (pin "9") (pinfunction "C_9") (pintype "input"))
      (node (ref "X6") (pin "4") (pinfunction "4_4") (pintype "passive"))
    )
    (net (code "9") (name "AGND") (class "Default")
      (node (ref "C1") (pin "1") (pinfunction "1_1") (pintype "passive"))
      (node (ref "C107") (pin "1") (pinfunction "1_1") (pintype "passive"))
      (node (ref "C108") (pin "1") (pinfunction "1_1") (pintype "passive"))
      (node (ref "C109") (pin "1") (pinfunction "1_1") (pintype "passive"))
      (node (ref "C11") (pin "1") (pinfunction "1_1") (pintype "passive"))
      (node (ref "C110") (pin "1") (pinfunction "1_1") (pintype "passive"))
      (node (ref "C111") (pin "1") (pinfunction "1_1") (pintype "passive"))
      (node (ref "C112") (pin "2") (pinfunction "2_2") (pintype "passive"))
      (node (ref "C113") (pin "1") (pinfunction "1_1") (pintype "passive"))
      (node (ref "C114") (pin "1") (pinfunction "1_1") (pintype "passive"))
      (node (ref "C115") (pin "1") (pinfunction "1_1") (pintype "passive"))
      (node (ref "C116") (pin "1") (pinfunction "1_1") (pintype "passive"))
      (node (ref "C117") (pin "1") (pinfunction "1_1") (pintype "passive"))
      (node (ref "C118") (pin "2") (pinfunction "2_2") (pintype "passive"))
      (node (ref "C119") (pin "1") (pinfunction "1_1") (pintype "passive"))
      (node (ref "C12") (pin "1") (pinfunction "1_1") (pintype "passive"))
      (node (ref "C13") (pin "1") (pinfunction "1_1") (pintype "passive"))
      (node (ref "C14") (pin "2") (pinfunction "2_2") (pintype "passive"))
      (node (ref "C15") (pin "1") (pinfunction "1_1") (pintype "passive"))
      (node (ref "C16") (pin "1") (pinfunction "1_1") (pintype "passive"))
      (node (ref "C17") (pin "1") (pinfunction "1_1") (pintype "passive"))
      (node (ref "C18") (pin "1") (pinfunction "1_1") (pintype "passive"))
      (node (ref "C2") (pin "1") (pinfunction "1_1") (pintype "passive"))
      (node (ref "C25") (pin "1") (pinfunction "1_1") (pintype "passive"))
      (node (ref "C26") (pin "2") (pinfunction "2_2") (pintype "passive"))
      (node (ref "C27") (pin "1") (pinfunction "1_1") (pintype "passive"))
      (node (ref "C28") (pin "1") (pinfunction "1_1") (pintype "passive"))
      (node (ref "C29") (pin "1") (pinfunction "1_1") (pintype "passive"))
      (node (ref "C3") (pin "1") (pinfunction "1_1") (pintype "passive"))
      (node (ref "C30") (pin "1") (pinfunction "1_1") (pintype "passive"))
      (node (ref "C31") (pin "1") (pinfunction "1_1") (pintype "passive"))
      (node (ref "C32") (pin "1") (pinfunction "1_1") (pintype "passive"))
      (node (ref "C33") (pin "2") (pinfunction "2_2") (pintype "passive"))
      (node (ref "C34") (pin "1") (pinfunction "1_1") (pintype "passive"))
      (node (ref "C35") (pin "1") (pinfunction "1_1") (pintype "passive"))
      (node (ref "C36") (pin "1") (pinfunction "1_1") (pintype "passive"))
      (node (ref "C37") (pin "1") (pinfunction "1_1") (pintype "passive"))
      (node (ref "C38") (pin "1") (pinfunction "1_1") (pintype "passive"))
      (node (ref "C39") (pin "2") (pinfunction "2_2") (pintype "passive"))
      (node (ref "C4") (pin "2") (pinfunction "2_2") (pintype "passive"))
      (node (ref "C41") (pin "1") (pinfunction "1_1") (pintype "passive"))
      (node (ref "C42") (pin "1") (pinfunction "1_1") (pintype "passive"))
      (node (ref "C43") (pin "1") (pinfunction "1_1") (pintype "passive"))
      (node (ref "C44") (pin "1") (pinfunction "1_1") (pintype "passive"))
      (node (ref "C45") (pin "1") (pinfunction "1_1") (pintype "passive"))
      (node (ref "C46") (pin "1") (pinfunction "1_1") (pintype "passive"))
      (node (ref "C47") (pin "2") (pinfunction "2_2") (pintype "passive"))
      (node (ref "C48") (pin "1") (pinfunction "1_1") (pintype "passive"))
      (node (ref "C49") (pin "1") (pinfunction "1_1") (pintype "passive"))
      (node (ref "C5") (pin "2") (pinfunction "2_2") (pintype "passive"))
      (node (ref "C50") (pin "1") (pinfunction "1_1") (pintype "passive"))
      (node (ref "C51") (pin "1") (pinfunction "1_1") (pintype "passive"))
      (node (ref "C52") (pin "1") (pinfunction "1_1") (pintype "passive"))
      (node (ref "C53") (pin "2") (pinfunction "2_2") (pintype "passive"))
      (node (ref "C54") (pin "1") (pinfunction "1_1") (pintype "passive"))
      (node (ref "C55") (pin "1") (pinfunction "1_1") (pintype "passive"))
      (node (ref "C56") (pin "1") (pinfunction "1_1") (pintype "passive"))
      (node (ref "C57") (pin "1") (pinfunction "1_1") (pintype "passive"))
      (node (ref "C58") (pin "1") (pinfunction "1_1") (pintype "passive"))
      (node (ref "C59") (pin "1") (pinfunction "1_1") (pintype "passive"))
      (node (ref "C6") (pin "1") (pinfunction "1_1") (pintype "passive"))
      (node (ref "C60") (pin "2") (pinfunction "2_2") (pintype "passive"))
      (node (ref "C61") (pin "1") (pinfunction "1_1") (pintype "passive"))
      (node (ref "C62") (pin "1") (pinfunction "1_1") (pintype "passive"))
      (node (ref "C63") (pin "1") (pinfunction "1_1") (pintype "passive"))
      (node (ref "C64") (pin "1") (pinfunction "1_1") (pintype "passive"))
      (node (ref "C65") (pin "1") (pinfunction "1_1") (pintype "passive"))
      (node (ref "C66") (pin "2") (pinfunction "2_2") (pintype "passive"))
      (node (ref "C67") (pin "1") (pinfunction "1_1") (pintype "passive"))
      (node (ref "C68") (pin "1") (pinfunction "1_1") (pintype "passive"))
      (node (ref "C69") (pin "1") (pinfunction "1_1") (pintype "passive"))
      (node (ref "C7") (pin "1") (pinfunction "1_1") (pintype "passive"))
      (node (ref "C70") (pin "1") (pinfunction "1_1") (pintype "passive"))
      (node (ref "C71") (pin "1") (pinfunction "1_1") (pintype "passive"))
      (node (ref "C72") (pin "1") (pinfunction "1_1") (pintype "passive"))
      (node (ref "C73") (pin "2") (pinfunction "2_2") (pintype "passive"))
      (node (ref "C74") (pin "1") (pinfunction "1_1") (pintype "passive"))
      (node (ref "C75") (pin "1") (pinfunction "1_1") (pintype "passive"))
      (node (ref "C76") (pin "1") (pinfunction "1_1") (pintype "passive"))
      (node (ref "C77") (pin "1") (pinfunction "1_1") (pintype "passive"))
      (node (ref "C78") (pin "1") (pinfunction "1_1") (pintype "passive"))
      (node (ref "C79") (pin "2") (pinfunction "2_2") (pintype "passive"))
      (node (ref "C8") (pin "1") (pinfunction "1_1") (pintype "passive"))
      (node (ref "C80") (pin "1") (pinfunction "1_1") (pintype "passive"))
      (node (ref "C81") (pin "1") (pinfunction "1_1") (pintype "passive"))
      (node (ref "C82") (pin "1") (pinfunction "1_1") (pintype "passive"))
      (node (ref "C83") (pin "1") (pinfunction "1_1") (pintype "passive"))
      (node (ref "C84") (pin "1") (pinfunction "1_1") (pintype "passive"))
      (node (ref "C85") (pin "1") (pinfunction "1_1") (pintype "passive"))
      (node (ref "C86") (pin "2") (pinfunction "2_2") (pintype "passive"))
      (node (ref "C87") (pin "1") (pinfunction "1_1") (pintype "passive"))
      (node (ref "C88") (pin "1") (pinfunction "1_1") (pintype "passive"))
      (node (ref "C89") (pin "1") (pinfunction "1_1") (pintype "passive"))
      (node (ref "C9") (pin "2") (pinfunction "2_2") (pintype "passive"))
      (node (ref "C90") (pin "1") (pinfunction "1_1") (pintype "passive"))
      (node (ref "C91") (pin "1") (pinfunction "1_1") (pintype "passive"))
      (node (ref "C92") (pin "2") (pinfunction "2_2") (pintype "passive"))
      (node (ref "C93") (pin "1") (pinfunction "1_1") (pintype "passive"))
      (node (ref "IC1") (pin "7") (pinfunction "VEE_7") (pintype "power_in"))
      (node (ref "IC1") (pin "8") (pinfunction "GND_8") (pintype "power_in"))
      (node (ref "IC11") (pin "7") (pinfunction "VEE_7") (pintype "power_in"))
      (node (ref "IC11") (pin "8") (pinfunction "GND_8") (pintype "power_in"))
      (node (ref "IC14") (pin "7") (pinfunction "VEE_7") (pintype "power_in"))
      (node (ref "IC14") (pin "8") (pinfunction "GND_8") (pintype "power_in"))
      (node (ref "IC17") (pin "7") (pinfunction "VEE_7") (pintype "power_in"))
      (node (ref "IC17") (pin "8") (pinfunction "GND_8") (pintype "power_in"))
      (node (ref "IC2") (pin "14") (pinfunction "RSTSEL_14") (pintype "bidirectional"))
      (node (ref "IC2") (pin "15") (pinfunction "~{ENABLE}_15") (pintype "bidirectional"))
      (node (ref "IC2") (pin "5") (pinfunction "VREF_L_5") (pintype "bidirectional"))
      (node (ref "IC2") (pin "6") (pinfunction "GND_6") (pintype "bidirectional"))
      (node (ref "IC20") (pin "7") (pinfunction "VEE_7") (pintype "power_in"))
      (node (ref "IC20") (pin "8") (pinfunction "GND_8") (pintype "power_in"))
      (node (ref "IC26") (pin "7") (pinfunction "VEE_7") (pintype "power_in"))
      (node (ref "IC26") (pin "8") (pinfunction "GND_8") (pintype "power_in"))
      (node (ref "IC5") (pin "2") (pinfunction "GND_2") (pintype "passive"))
      (node (ref "IC5") (pin "2@1") (pinfunction "GND_2@1") (pintype "passive"))
      (node (ref "IC7") (pin "7") (pinfunction "VEE_7") (pintype "power_in"))
      (node (ref "IC7") (pin "8") (pinfunction "GND_8") (pintype "power_in"))
      (node (ref "R2") (pin "1") (pinfunction "1_1") (pintype "passive"))
      (node (ref "R3") (pin "1") (pinfunction "1_1") (pintype "passive"))
      (node (ref "R5") (pin "1") (pinfunction "1_1") (pintype "passive"))
      (node (ref "R7") (pin "1") (pinfunction "1_1") (pintype "passive"))
      (node (ref "X6") (pin "14") (pinfunction "14_14") (pintype "passive"))
    )
    (net (code "10") (name "DAC_1") (class "Default")
      (node (ref "IC26") (pin "3") (pinfunction "X_3") (pintype "bidirectional"))
      (node (ref "R9") (pin "2") (pinfunction "2_2") (pintype "passive"))
    )
    (net (code "11") (name "DAC_2") (class "Default")
      (node (ref "IC17") (pin "3") (pinfunction "X_3") (pintype "bidirectional"))
      (node (ref "IC20") (pin "3") (pinfunction "X_3") (pintype "bidirectional"))
      (node (ref "R10") (pin "2") (pinfunction "2_2") (pintype "passive"))
    )
    (net (code "12") (name "DAC_3") (class "Default")
      (node (ref "IC14") (pin "3") (pinfunction "X_3") (pintype "bidirectional"))
      (node (ref "IC7") (pin "3") (pinfunction "X_3") (pintype "bidirectional"))
      (node (ref "R11") (pin "2") (pinfunction "2_2") (pintype "passive"))
    )
    (net (code "13") (name "DAC_4") (class "Default")
      (node (ref "IC1") (pin "3") (pinfunction "X_3") (pintype "bidirectional"))
      (node (ref "IC11") (pin "3") (pinfunction "X_3") (pintype "bidirectional"))
      (node (ref "R12") (pin "2") (pinfunction "2_2") (pintype "passive"))
    )
    (net (code "14") (name "DAC_RAW_1") (class "Default")
      (node (ref "IC2") (pin "1") (pinfunction "OUT_A_1") (pintype "bidirectional"))
      (node (ref "IC8") (pin "3") (pinfunction "+IN_3") (pintype "input"))
    )
    (net (code "15") (name "DAC_RAW_2") (class "Default")
      (node (ref "IC2") (pin "2") (pinfunction "OUT_B_2") (pintype "bidirectional"))
      (node (ref "IC8") (pin "5") (pinfunction "+IN_5") (pintype "input"))
    )
    (net (code "16") (name "DAC_RAW_3") (class "Default")
      (node (ref "IC2") (pin "7") (pinfunction "OUT_C_7") (pintype "bidirectional"))
      (node (ref "IC8") (pin "10") (pinfunction "+IN_10") (pintype "input"))
    )
    (net (code "17") (name "DAC_RAW_4") (class "Default")
      (node (ref "IC2") (pin "8") (pinfunction "OUT_D_8") (pintype "bidirectional"))
      (node (ref "IC8") (pin "12") (pinfunction "+IN_12") (pintype "input"))
    )
    (net (code "18") (name "INH_0") (class "Default")
      (node (ref "IC1") (pin "6") (pinfunction "INH_6") (pintype "input"))
      (node (ref "IC20") (pin "6") (pinfunction "INH_6") (pintype "input"))
      (node (ref "IC26") (pin "6") (pinfunction "INH_6") (pintype "input"))
      (node (ref "IC7") (pin "6") (pinfunction "INH_6") (pintype "input"))
      (node (ref "X6") (pin "3") (pinfunction "3_3") (pintype "passive"))
    )
    (net (code "19") (name "INH_1") (class "Default")
      (node (ref "IC11") (pin "6") (pinfunction "INH_6") (pintype "input"))
      (node (ref "IC14") (pin "6") (pinfunction "INH_6") (pintype "input"))
      (node (ref "IC17") (pin "6") (pinfunction "INH_6") (pintype "input"))
      (node (ref "X6") (pin "6") (pinfunction "6_6") (pintype "passive"))
    )
    (net (code "20") (name "IN_0") (class "Default")
      (node (ref "C13") (pin "2") (pinfunction "2_2") (pintype "passive"))
      (node (ref "IC1") (pin "13") (pinfunction "X0_13") (pintype "bidirectional"))
      (node (ref "IC3") (pin "12") (pinfunction "+IN_12") (pintype "input"))
    )
    (net (code "21") (name "IN_1") (class "Default")
      (node (ref "C12") (pin "2") (pinfunction "2_2") (pintype "passive"))
      (node (ref "IC1") (pin "14") (pinfunction "X1_14") (pintype "bidirectional"))
      (node (ref "IC3") (pin "10") (pinfunction "+IN_10") (pintype "input"))
    )
    (net (code "22") (name "IN_2") (class "Default")
      (node (ref "C11") (pin "2") (pinfunction "2_2") (pintype "passive"))
      (node (ref "IC1") (pin "15") (pinfunction "X2_15") (pintype "bidirectional"))
      (node (ref "IC3") (pin "5") (pinfunction "+IN_5") (pintype "input"))
    )
    (net (code "23") (name "IN_3") (class "Default")
      (node (ref "C7") (pin "2") (pinfunction "2_2") (pintype "passive"))
      (node (ref "IC1") (pin "12") (pinfunction "X3_12") (pintype "bidirectional"))
      (node (ref "IC3") (pin "3") (pinfunction "+IN_3") (pintype "input"))
    )
    (net (code "24") (name "IN_4") (class "Default")
      (node (ref "C25") (pin "2") (pinfunction "2_2") (pintype "passive"))
      (node (ref "IC1") (pin "1") (pinfunction "X4_1") (pintype "bidirectional"))
      (node (ref "IC6") (pin "12") (pinfunction "+IN_12") (pintype "input"))
    )
    (net (code "25") (name "IN_5") (class "Default")
      (node (ref "C18") (pin "2") (pinfunction "2_2") (pintype "passive"))
      (node (ref "IC1") (pin "5") (pinfunction "X5_5") (pintype "bidirectional"))
      (node (ref "IC6") (pin "10") (pinfunction "+IN_10") (pintype "input"))
    )
    (net (code "26") (name "IN_6") (class "Default")
      (node (ref "C17") (pin "2") (pinfunction "2_2") (pintype "passive"))
      (node (ref "IC1") (pin "2") (pinfunction "X6_2") (pintype "bidirectional"))
      (node (ref "IC6") (pin "5") (pinfunction "+IN_5") (pintype "input"))
    )
    (net (code "27") (name "IN_7") (class "Default")
      (node (ref "C16") (pin "2") (pinfunction "2_2") (pintype "passive"))
      (node (ref "IC1") (pin "4") (pinfunction "X7_4") (pintype "bidirectional"))
      (node (ref "IC6") (pin "3") (pinfunction "+IN_3") (pintype "input"))
    )
    (net (code "28") (name "IN_8") (class "Default")
      (node (ref "C46") (pin "2") (pinfunction "2_2") (pintype "passive"))
      (node (ref "IC11") (pin "13") (pinfunction "X0_13") (pintype "bidirectional"))
      (node (ref "IC12") (pin "12") (pinfunction "+IN_12") (pintype "input"))
    )
    (net (code "29") (name "IN_9") (class "Default")
      (node (ref "C45") (pin "2") (pinfunction "2_2") (pintype "passive"))
      (node (ref "IC11") (pin "14") (pinfunction "X1_14") (pintype "bidirectional"))
      (node (ref "IC12") (pin "10") (pinfunction "+IN_10") (pintype "input"))
    )
    (net (code "30") (name "IN_10") (class "Default")
      (node (ref "C44") (pin "2") (pinfunction "2_2") (pintype "passive"))
      (node (ref "IC11") (pin "15") (pinfunction "X2_15") (pintype "bidirectional"))
      (node (ref "IC12") (pin "5") (pinfunction "+IN_5") (pintype "input"))
    )
    (net (code "31") (name "IN_11") (class "Default")
      (node (ref "C43") (pin "2") (pinfunction "2_2") (pintype "passive"))
      (node (ref "IC11") (pin "12") (pinfunction "X3_12") (pintype "bidirectional"))
      (node (ref "IC12") (pin "3") (pinfunction "+IN_3") (pintype "input"))
    )
    (net (code "32") (name "IN_12") (class "Default")
      (node (ref "C52") (pin "2") (pinfunction "2_2") (pintype "passive"))
      (node (ref "IC11") (pin "1") (pinfunction "X4_1") (pintype "bidirectional"))
      (node (ref "IC13") (pin "12") (pinfunction "+IN_12") (pintype "input"))
    )
    (net (code "33") (name "IN_13") (class "Default")
      (node (ref "C51") (pin "2") (pinfunction "2_2") (pintype "passive"))
      (node (ref "IC11") (pin "5") (pinfunction "X5_5") (pintype "bidirectional"))
      (node (ref "IC13") (pin "10") (pinfunction "+IN_10") (pintype "input"))
    )
    (net (code "34") (name "IN_14") (class "Default")
      (node (ref "C50") (pin "2") (pinfunction "2_2") (pintype "passive"))
      (node (ref "IC11") (pin "2") (pinfunction "X6_2") (pintype "bidirectional"))
      (node (ref "IC13") (pin "5") (pinfunction "+IN_5") (pintype "input"))
    )
    (net (code "35") (name "IN_15") (class "Default")
      (node (ref "C49") (pin "2") (pinfunction "2_2") (pintype "passive"))
      (node (ref "IC11") (pin "4") (pinfunction "X7_4") (pintype "bidirectional"))
      (node (ref "IC13") (pin "3") (pinfunction "+IN_3") (pintype "input"))
    )
    (net (code "36") (name "IN_16") (class "Default")
      (node (ref "C32") (pin "2") (pinfunction "2_2") (pintype "passive"))
      (node (ref "IC7") (pin "13") (pinfunction "X0_13") (pintype "bidirectional"))
      (node (ref "IC9") (pin "12") (pinfunction "+IN_12") (pintype "input"))
    )
    (net (code "37") (name "IN_17") (class "Default")
      (node (ref "C31") (pin "2") (pinfunction "2_2") (pintype "passive"))
      (node (ref "IC7") (pin "14") (pinfunction "X1_14") (pintype "bidirectional"))
      (node (ref "IC9") (pin "10") (pinfunction "+IN_10") (pintype "input"))
    )
    (net (code "38") (name "IN_18") (class "Default")
      (node (ref "C30") (pin "2") (pinfunction "2_2") (pintype "passive"))
      (node (ref "IC7") (pin "15") (pinfunction "X2_15") (pintype "bidirectional"))
      (node (ref "IC9") (pin "5") (pinfunction "+IN_5") (pintype "input"))
    )
    (net (code "39") (name "IN_19") (class "Default")
      (node (ref "C29") (pin "2") (pinfunction "2_2") (pintype "passive"))
      (node (ref "IC7") (pin "12") (pinfunction "X3_12") (pintype "bidirectional"))
      (node (ref "IC9") (pin "3") (pinfunction "+IN_3") (pintype "input"))
    )
    (net (code "40") (name "IN_20") (class "Default")
      (node (ref "C38") (pin "2") (pinfunction "2_2") (pintype "passive"))
      (node (ref "IC10") (pin "12") (pinfunction "+IN_12") (pintype "input"))
      (node (ref "IC7") (pin "1") (pinfunction "X4_1") (pintype "bidirectional"))
    )
    (net (code "41") (name "IN_21") (class "Default")
      (node (ref "C37") (pin "2") (pinfunction "2_2") (pintype "passive"))
      (node (ref "IC10") (pin "10") (pinfunction "+IN_10") (pintype "input"))
      (node (ref "IC7") (pin "5") (pinfunction "X5_5") (pintype "bidirectional"))
    )
    (net (code "42") (name "IN_22") (class "Default")
      (node (ref "C36") (pin "2") (pinfunction "2_2") (pintype "passive"))
      (node (ref "IC10") (pin "5") (pinfunction "+IN_5") (pintype "input"))
      (node (ref "IC7") (pin "2") (pinfunction "X6_2") (pintype "bidirectional"))
    )
    (net (code "43") (name "IN_23") (class "Default")
      (node (ref "C35") (pin "2") (pinfunction "2_2") (pintype "passive"))
      (node (ref "IC10") (pin "3") (pinfunction "+IN_3") (pintype "input"))
      (node (ref "IC7") (pin "4") (pinfunction "X7_4") (pintype "bidirectional"))
    )
    (net (code "44") (name "IN_24") (class "Default")
      (node (ref "C59") (pin "2") (pinfunction "2_2") (pintype "passive"))
      (node (ref "IC14") (pin "13") (pinfunction "X0_13") (pintype "bidirectional"))
      (node (ref "IC15") (pin "12") (pinfunction "+IN_12") (pintype "input"))
    )
    (net (code "45") (name "IN_25") (class "Default")
      (node (ref "C58") (pin "2") (pinfunction "2_2") (pintype "passive"))
      (node (ref "IC14") (pin "14") (pinfunction "X1_14") (pintype "bidirectional"))
      (node (ref "IC15") (pin "10") (pinfunction "+IN_10") (pintype "input"))
    )
    (net (code "46") (name "IN_26") (class "Default")
      (node (ref "C57") (pin "2") (pinfunction "2_2") (pintype "passive"))
      (node (ref "IC14") (pin "15") (pinfunction "X2_15") (pintype "bidirectional"))
      (node (ref "IC15") (pin "5") (pinfunction "+IN_5") (pintype "input"))
    )
    (net (code "47") (name "IN_27") (class "Default")
      (node (ref "C56") (pin "2") (pinfunction "2_2") (pintype "passive"))
      (node (ref "IC14") (pin "12") (pinfunction "X3_12") (pintype "bidirectional"))
      (node (ref "IC15") (pin "3") (pinfunction "+IN_3") (pintype "input"))
    )
    (net (code "48") (name "IN_28") (class "Default")
      (node (ref "C65") (pin "2") (pinfunction "2_2") (pintype "passive"))
      (node (ref "IC14") (pin "1") (pinfunction "X4_1") (pintype "bidirectional"))
      (node (ref "IC16") (pin "12") (pinfunction "+IN_12") (pintype "input"))
    )
    (net (code "49") (name "IN_29") (class "Default")
      (node (ref "C64") (pin "2") (pinfunction "2_2") (pintype "passive"))
      (node (ref "IC14") (pin "5") (pinfunction "X5_5") (pintype "bidirectional"))
      (node (ref "IC16") (pin "10") (pinfunction "+IN_10") (pintype "input"))
    )
    (net (code "50") (name "IN_30") (class "Default")
      (node (ref "C63") (pin "2") (pinfunction "2_2") (pintype "passive"))
      (node (ref "IC14") (pin "2") (pinfunction "X6_2") (pintype "bidirectional"))
      (node (ref "IC16") (pin "5") (pinfunction "+IN_5") (pintype "input"))
    )
    (net (code "51") (name "IN_31") (class "Default")
      (node (ref "C62") (pin "2") (pinfunction "2_2") (pintype "passive"))
      (node (ref "IC14") (pin "4") (pinfunction "X7_4") (pintype "bidirectional"))
      (node (ref "IC16") (pin "3") (pinfunction "+IN_3") (pintype "input"))
    )
    (net (code "52") (name "IN_32") (class "Default")
      (node (ref "C85") (pin "2") (pinfunction "2_2") (pintype "passive"))
      (node (ref "IC20") (pin "13") (pinfunction "X0_13") (pintype "bidirectional"))
      (node (ref "IC21") (pin "12") (pinfunction "+IN_12") (pintype "input"))
    )
    (net (code "53") (name "IN_33") (class "Default")
      (node (ref "C84") (pin "2") (pinfunction "2_2") (pintype "passive"))
      (node (ref "IC20") (pin "14") (pinfunction "X1_14") (pintype "bidirectional"))
      (node (ref "IC21") (pin "10") (pinfunction "+IN_10") (pintype "input"))
    )
    (net (code "54") (name "IN_34") (class "Default")
      (node (ref "C83") (pin "2") (pinfunction "2_2") (pintype "passive"))
      (node (ref "IC20") (pin "15") (pinfunction "X2_15") (pintype "bidirectional"))
      (node (ref "IC21") (pin "5") (pinfunction "+IN_5") (pintype "input"))
    )
    (net (code "55") (name "IN_35") (class "Default")
      (node (ref "C82") (pin "2") (pinfunction "2_2") (pintype "passive"))
      (node (ref "IC20") (pin "12") (pinfunction "X3_12") (pintype "bidirectional"))
      (node (ref "IC21") (pin "3") (pinfunction "+IN_3") (pintype "input"))
    )
    (net (code "56") (name "IN_36") (class "Default")
      (node (ref "C91") (pin "2") (pinfunction "2_2") (pintype "passive"))
      (node (ref "IC20") (pin "1") (pinfunction "X4_1") (pintype "bidirectional"))
      (node (ref "IC22") (pin "12") (pinfunction "+IN_12") (pintype "input"))
    )
    (net (code "57") (name "IN_37") (class "Default")
      (node (ref "C90") (pin "2") (pinfunction "2_2") (pintype "passive"))
      (node (ref "IC20") (pin "5") (pinfunction "X5_5") (pintype "bidirectional"))
      (node (ref "IC22") (pin "10") (pinfunction "+IN_10") (pintype "input"))
    )
    (net (code "58") (name "IN_38") (class "Default")
      (node (ref "C89") (pin "2") (pinfunction "2_2") (pintype "passive"))
      (node (ref "IC20") (pin "2") (pinfunction "X6_2") (pintype "bidirectional"))
      (node (ref "IC22") (pin "5") (pinfunction "+IN_5") (pintype "input"))
    )
    (net (code "59") (name "IN_39") (class "Default")
      (node (ref "C88") (pin "2") (pinfunction "2_2") (pintype "passive"))
      (node (ref "IC20") (pin "4") (pinfunction "X7_4") (pintype "bidirectional"))
      (node (ref "IC22") (pin "3") (pinfunction "+IN_3") (pintype "input"))
    )
    (net (code "60") (name "IN_40") (class "Default")
      (node (ref "C72") (pin "2") (pinfunction "2_2") (pintype "passive"))
      (node (ref "IC17") (pin "13") (pinfunction "X0_13") (pintype "bidirectional"))
      (node (ref "IC18") (pin "12") (pinfunction "+IN_12") (pintype "input"))
    )
    (net (code "61") (name "IN_41") (class "Default")
      (node (ref "C71") (pin "2") (pinfunction "2_2") (pintype "passive"))
      (node (ref "IC17") (pin "14") (pinfunction "X1_14") (pintype "bidirectional"))
      (node (ref "IC18") (pin "10") (pinfunction "+IN_10") (pintype "input"))
    )
    (net (code "62") (name "IN_42") (class "Default")
      (node (ref "C70") (pin "2") (pinfunction "2_2") (pintype "passive"))
      (node (ref "IC17") (pin "15") (pinfunction "X2_15") (pintype "bidirectional"))
      (node (ref "IC18") (pin "5") (pinfunction "+IN_5") (pintype "input"))
    )
    (net (code "63") (name "IN_43") (class "Default")
      (node (ref "C69") (pin "2") (pinfunction "2_2") (pintype "passive"))
      (node (ref "IC17") (pin "12") (pinfunction "X3_12") (pintype "bidirectional"))
      (node (ref "IC18") (pin "3") (pinfunction "+IN_3") (pintype "input"))
    )
    (net (code "64") (name "IN_44") (class "Default")
      (node (ref "C78") (pin "2") (pinfunction "2_2") (pintype "passive"))
      (node (ref "IC17") (pin "1") (pinfunction "X4_1") (pintype "bidirectional"))
      (node (ref "IC19") (pin "12") (pinfunction "+IN_12") (pintype "input"))
    )
    (net (code "65") (name "IN_45") (class "Default")
      (node (ref "C77") (pin "2") (pinfunction "2_2") (pintype "passive"))
      (node (ref "IC17") (pin "5") (pinfunction "X5_5") (pintype "bidirectional"))
      (node (ref "IC19") (pin "10") (pinfunction "+IN_10") (pintype "input"))
    )
    (net (code "66") (name "IN_46") (class "Default")
      (node (ref "C76") (pin "2") (pinfunction "2_2") (pintype "passive"))
      (node (ref "IC17") (pin "2") (pinfunction "X6_2") (pintype "bidirectional"))
      (node (ref "IC19") (pin "5") (pinfunction "+IN_5") (pintype "input"))
    )
    (net (code "67") (name "IN_47") (class "Default")
      (node (ref "C75") (pin "2") (pinfunction "2_2") (pintype "passive"))
      (node (ref "IC17") (pin "4") (pinfunction "X7_4") (pintype "bidirectional"))
      (node (ref "IC19") (pin "3") (pinfunction "+IN_3") (pintype "input"))
    )
    (net (code "68") (name "IN_48") (class "Default")
      (node (ref "C111") (pin "2") (pinfunction "2_2") (pintype "passive"))
      (node (ref "IC26") (pin "13") (pinfunction "X0_13") (pintype "bidirectional"))
      (node (ref "IC27") (pin "12") (pinfunction "+IN_12") (pintype "input"))
    )
    (net (code "69") (name "IN_49") (class "Default")
      (node (ref "C110") (pin "2") (pinfunction "2_2") (pintype "passive"))
      (node (ref "IC26") (pin "14") (pinfunction "X1_14") (pintype "bidirectional"))
      (node (ref "IC27") (pin "10") (pinfunction "+IN_10") (pintype "input"))
    )
    (net (code "70") (name "IN_50") (class "Default")
      (node (ref "C109") (pin "2") (pinfunction "2_2") (pintype "passive"))
      (node (ref "IC26") (pin "15") (pinfunction "X2_15") (pintype "bidirectional"))
      (node (ref "IC27") (pin "5") (pinfunction "+IN_5") (pintype "input"))
    )
    (net (code "71") (name "IN_51") (class "Default")
      (node (ref "C108") (pin "2") (pinfunction "2_2") (pintype "passive"))
      (node (ref "IC26") (pin "12") (pinfunction "X3_12") (pintype "bidirectional"))
      (node (ref "IC27") (pin "3") (pinfunction "+IN_3") (pintype "input"))
    )
    (net (code "72") (name "IN_52") (class "Default")
      (node (ref "C117") (pin "2") (pinfunction "2_2") (pintype "passive"))
      (node (ref "IC26") (pin "1") (pinfunction "X4_1") (pintype "bidirectional"))
      (node (ref "IC28") (pin "12") (pinfunction "+IN_12") (pintype "input"))
    )
    (net (code "73") (name "IN_53") (class "Default")
      (node (ref "C116") (pin "2") (pinfunction "2_2") (pintype "passive"))
      (node (ref "IC26") (pin "5") (pinfunction "X5_5") (pintype "bidirectional"))
      (node (ref "IC28") (pin "10") (pinfunction "+IN_10") (pintype "input"))
    )
    (net (code "74") (name "IN_54") (class "Default")
      (node (ref "C115") (pin "2") (pinfunction "2_2") (pintype "passive"))
      (node (ref "IC26") (pin "2") (pinfunction "X6_2") (pintype "bidirectional"))
      (node (ref "IC28") (pin "5") (pinfunction "+IN_5") (pintype "input"))
    )
    (net (code "75") (name "IN_55") (class "Default")
      (node (ref "C114") (pin "2") (pinfunction "2_2") (pintype "passive"))
      (node (ref "IC26") (pin "4") (pinfunction "X7_4") (pintype "bidirectional"))
      (node (ref "IC28") (pin "3") (pinfunction "+IN_3") (pintype "input"))
    )
    (net (code "76") (name "LDAC") (class "Default")
      (node (ref "IC2") (pin "16") (pinfunction "LDAC_16") (pintype "bidirectional"))
      (node (ref "X6") (pin "9") (pinfunction "9_9") (pintype "passive"))
    )
    (net (code "77") (name "Net-(IC2-IOVDD)") (class "Default")
      (node (ref "C9") (pin "1") (pinfunction "1_1") (pintype "passive"))
      (node (ref "IC2") (pin "12") (pinfunction "IOVDD_12") (pintype "power_in"))
      (node (ref "JP1") (pin "2") (pinfunction "2_2") (pintype "passive"))
    )
    (net (code "78") (name "Net-(IC8A--IN)") (class "Default")
      (node (ref "IC8") (pin "2") (pinfunction "-IN_2") (pintype "input"))
      (node (ref "R1") (pin "1") (pinfunction "1_1") (pintype "passive"))
      (node (ref "R2") (pin "2") (pinfunction "2_2") (pintype "passive"))
    )
    (net (code "79") (name "Net-(IC8A-OUT)") (class "Default")
      (node (ref "IC8") (pin "1") (pinfunction "OUT_1") (pintype "output"))
      (node (ref "R1") (pin "2") (pinfunction "2_2") (pintype "passive"))
      (node (ref "R9") (pin "1") (pinfunction "1_1") (pintype "passive"))
    )
    (net (code "80") (name "Net-(IC8B--IN)") (class "Default")
      (node (ref "IC8") (pin "6") (pinfunction "-IN_6") (pintype "input"))
      (node (ref "R3") (pin "2") (pinfunction "2_2") (pintype "passive"))
      (node (ref "R4") (pin "1") (pinfunction "1_1") (pintype "passive"))
    )
    (net (code "81") (name "Net-(IC8B-OUT)") (class "Default")
      (node (ref "IC8") (pin "7") (pinfunction "OUT_7") (pintype "output"))
      (node (ref "R10") (pin "1") (pinfunction "1_1") (pintype "passive"))
      (node (ref "R4") (pin "2") (pinfunction "2_2") (pintype "passive"))
    )
    (net (code "82") (name "Net-(IC8C--IN)") (class "Default")
      (node (ref "IC8") (pin "9") (pinfunction "-IN_9") (pintype "input"))
      (node (ref "R5") (pin "2") (pinfunction "2_2") (pintype "passive"))
      (node (ref "R6") (pin "1") (pinfunction "1_1") (pintype "passive"))
    )
    (net (code "83") (name "Net-(IC8C-OUT)") (class "Default")
      (node (ref "IC8") (pin "8") (pinfunction "OUT_8") (pintype "output"))
      (node (ref "R11") (pin "1") (pinfunction "1_1") (pintype "passive"))
      (node (ref "R6") (pin "2") (pinfunction "2_2") (pintype "passive"))
    )
    (net (code "84") (name "Net-(IC8D--IN)") (class "Default")
      (node (ref "IC8") (pin "13") (pinfunction "-IN_13") (pintype "input"))
      (node (ref "R7") (pin "2") (pinfunction "2_2") (pintype "passive"))
      (node (ref "R8") (pin "1") (pinfunction "1_1") (pintype "passive"))
    )
    (net (code "85") (name "Net-(IC8D-OUT)") (class "Default")
      (node (ref "IC8") (pin "14") (pinfunction "OUT_14") (pintype "output"))
      (node (ref "R12") (pin "1") (pinfunction "1_1") (pintype "passive"))
      (node (ref "R8") (pin "2") (pinfunction "2_2") (pintype "passive"))
    )
    (net (code "86") (name "OUT_0") (class "Default")
      (node (ref "IC3") (pin "13") (pinfunction "-IN_13") (pintype "input"))
      (node (ref "IC3") (pin "14") (pinfunction "OUT_14") (pintype "output"))
      (node (ref "U$2") (pin "1") (pinfunction "1_1") (pintype "passive"))
      (node (ref "U$2") (pin "2") (pinfunction "2_2") (pintype "passive"))
    )
    (net (code "87") (name "OUT_1") (class "Default")
      (node (ref "IC3") (pin "8") (pinfunction "OUT_8") (pintype "output"))
      (node (ref "IC3") (pin "9") (pinfunction "-IN_9") (pintype "input"))
      (node (ref "U$2") (pin "3") (pinfunction "3_3") (pintype "passive"))
      (node (ref "U$2") (pin "4") (pinfunction "4_4") (pintype "passive"))
    )
    (net (code "88") (name "OUT_2") (class "Default")
      (node (ref "IC3") (pin "6") (pinfunction "-IN_6") (pintype "input"))
      (node (ref "IC3") (pin "7") (pinfunction "OUT_7") (pintype "output"))
      (node (ref "U$2") (pin "5") (pinfunction "5_5") (pintype "passive"))
      (node (ref "U$2") (pin "6") (pinfunction "6_6") (pintype "passive"))
    )
    (net (code "89") (name "OUT_3") (class "Default")
      (node (ref "IC3") (pin "1") (pinfunction "OUT_1") (pintype "output"))
      (node (ref "IC3") (pin "2") (pinfunction "-IN_2") (pintype "input"))
      (node (ref "U$2") (pin "7") (pinfunction "7_7") (pintype "passive"))
      (node (ref "U$2") (pin "8") (pinfunction "8_8") (pintype "passive"))
    )
    (net (code "90") (name "OUT_4") (class "Default")
      (node (ref "IC6") (pin "13") (pinfunction "-IN_13") (pintype "input"))
      (node (ref "IC6") (pin "14") (pinfunction "OUT_14") (pintype "output"))
      (node (ref "U$2") (pin "10") (pinfunction "10_10") (pintype "passive"))
      (node (ref "U$2") (pin "9") (pinfunction "9_9") (pintype "passive"))
    )
    (net (code "91") (name "OUT_5") (class "Default")
      (node (ref "IC6") (pin "8") (pinfunction "OUT_8") (pintype "output"))
      (node (ref "IC6") (pin "9") (pinfunction "-IN_9") (pintype "input"))
      (node (ref "U$2") (pin "11") (pinfunction "11_11") (pintype "passive"))
      (node (ref "U$2") (pin "12") (pinfunction "12_12") (pintype "passive"))
    )
    (net (code "92") (name "OUT_6") (class "Default")
      (node (ref "IC6") (pin "6") (pinfunction "-IN_6") (pintype "input"))
      (node (ref "IC6") (pin "7") (pinfunction "OUT_7") (pintype "output"))
      (node (ref "U$2") (pin "13") (pinfunction "13_13") (pintype "passive"))
      (node (ref "U$2") (pin "14") (pinfunction "14_14") (pintype "passive"))
    )
    (net (code "93") (name "OUT_7") (class "Default")
      (node (ref "IC6") (pin "1") (pinfunction "OUT_1") (pintype "output"))
      (node (ref "IC6") (pin "2") (pinfunction "-IN_2") (pintype "input"))
      (node (ref "U$2") (pin "15") (pinfunction "15_15") (pintype "passive"))
      (node (ref "U$2") (pin "16") (pinfunction "16_16") (pintype "passive"))
    )
    (net (code "94") (name "OUT_8") (class "Default")
      (node (ref "IC12") (pin "13") (pinfunction "-IN_13") (pintype "input"))
      (node (ref "IC12") (pin "14") (pinfunction "OUT_14") (pintype "output"))
      (node (ref "U$2") (pin "17") (pinfunction "17_17") (pintype "passive"))
      (node (ref "U$2") (pin "18") (pinfunction "18_18") (pintype "passive"))
    )
    (net (code "95") (name "OUT_9") (class "Default")
      (node (ref "IC12") (pin "8") (pinfunction "OUT_8") (pintype "output"))
      (node (ref "IC12") (pin "9") (pinfunction "-IN_9") (pintype "input"))
      (node (ref "U$2") (pin "19") (pinfunction "19_19") (pintype "passive"))
      (node (ref "U$2") (pin "20") (pinfunction "20_20") (pintype "passive"))
    )
    (net (code "96") (name "OUT_10") (class "Default")
      (node (ref "IC12") (pin "6") (pinfunction "-IN_6") (pintype "input"))
      (node (ref "IC12") (pin "7") (pinfunction "OUT_7") (pintype "output"))
      (node (ref "U$2") (pin "21") (pinfunction "21_21") (pintype "passive"))
      (node (ref "U$2") (pin "22") (pinfunction "22_22") (pintype "passive"))
    )
    (net (code "97") (name "OUT_11") (class "Default")
      (node (ref "IC12") (pin "1") (pinfunction "OUT_1") (pintype "output"))
      (node (ref "IC12") (pin "2") (pinfunction "-IN_2") (pintype "input"))
      (node (ref "U$2") (pin "23") (pinfunction "23_23") (pintype "passive"))
      (node (ref "U$2") (pin "24") (pinfunction "24_24") (pintype "passive"))
    )
    (net (code "98") (name "OUT_12") (class "Default")
      (node (ref "IC13") (pin "13") (pinfunction "-IN_13") (pintype "input"))
      (node (ref "IC13") (pin "14") (pinfunction "OUT_14") (pintype "output"))
      (node (ref "U$2") (pin "25") (pinfunction "25_25") (pintype "passive"))
      (node (ref "U$2") (pin "26") (pinfunction "26_26") (pintype "passive"))
    )
    (net (code "99") (name "OUT_13") (class "Default")
      (node (ref "IC13") (pin "8") (pinfunction "OUT_8") (pintype "output"))
      (node (ref "IC13") (pin "9") (pinfunction "-IN_9") (pintype "input"))
      (node (ref "U$2") (pin "27") (pinfunction "27_27") (pintype "passive"))
      (node (ref "U$2") (pin "28") (pinfunction "28_28") (pintype "passive"))
    )
    (net (code "100") (name "OUT_14") (class "Default")
      (node (ref "IC13") (pin "6") (pinfunction "-IN_6") (pintype "input"))
      (node (ref "IC13") (pin "7") (pinfunction "OUT_7") (pintype "output"))
      (node (ref "U$2") (pin "29") (pinfunction "29_29") (pintype "passive"))
      (node (ref "U$2") (pin "30") (pinfunction "30_30") (pintype "passive"))
    )
    (net (code "101") (name "OUT_15") (class "Default")
      (node (ref "IC13") (pin "1") (pinfunction "OUT_1") (pintype "output"))
      (node (ref "IC13") (pin "2") (pinfunction "-IN_2") (pintype "input"))
      (node (ref "X5") (pin "1") (pinfunction "1_1") (pintype "passive"))
    )
    (net (code "102") (name "OUT_16") (class "Default")
      (node (ref "IC9") (pin "13") (pinfunction "-IN_13") (pintype "input"))
      (node (ref "IC9") (pin "14") (pinfunction "OUT_14") (pintype "output"))
      (node (ref "U$3") (pin "1") (pinfunction "1_1") (pintype "passive"))
      (node (ref "U$3") (pin "2") (pinfunction "2_2") (pintype "passive"))
    )
    (net (code "103") (name "OUT_17") (class "Default")
      (node (ref "IC9") (pin "8") (pinfunction "OUT_8") (pintype "output"))
      (node (ref "IC9") (pin "9") (pinfunction "-IN_9") (pintype "input"))
      (node (ref "U$3") (pin "3") (pinfunction "3_3") (pintype "passive"))
      (node (ref "U$3") (pin "4") (pinfunction "4_4") (pintype "passive"))
    )
    (net (code "104") (name "OUT_18") (class "Default")
      (node (ref "IC9") (pin "6") (pinfunction "-IN_6") (pintype "input"))
      (node (ref "IC9") (pin "7") (pinfunction "OUT_7") (pintype "output"))
      (node (ref "U$3") (pin "5") (pinfunction "5_5") (pintype "passive"))
      (node (ref "U$3") (pin "6") (pinfunction "6_6") (pintype "passive"))
    )
    (net (code "105") (name "OUT_19") (class "Default")
      (node (ref "IC9") (pin "1") (pinfunction "OUT_1") (pintype "output"))
      (node (ref "IC9") (pin "2") (pinfunction "-IN_2") (pintype "input"))
      (node (ref "U$3") (pin "7") (pinfunction "7_7") (pintype "passive"))
      (node (ref "U$3") (pin "8") (pinfunction "8_8") (pintype "passive"))
    )
    (net (code "106") (name "OUT_20") (class "Default")
      (node (ref "IC10") (pin "13") (pinfunction "-IN_13") (pintype "input"))
      (node (ref "IC10") (pin "14") (pinfunction "OUT_14") (pintype "output"))
      (node (ref "U$3") (pin "10") (pinfunction "10_10") (pintype "passive"))
      (node (ref "U$3") (pin "9") (pinfunction "9_9") (pintype "passive"))
    )
    (net (code "107") (name "OUT_21") (class "Default")
      (node (ref "IC10") (pin "8") (pinfunction "OUT_8") (pintype "output"))
      (node (ref "IC10") (pin "9") (pinfunction "-IN_9") (pintype "input"))
      (node (ref "U$3") (pin "11") (pinfunction "11_11") (pintype "passive"))
      (node (ref "U$3") (pin "12") (pinfunction "12_12") (pintype "passive"))
    )
    (net (code "108") (name "OUT_22") (class "Default")
      (node (ref "IC10") (pin "6") (pinfunction "-IN_6") (pintype "input"))
      (node (ref "IC10") (pin "7") (pinfunction "OUT_7") (pintype "output"))
      (node (ref "U$3") (pin "13") (pinfunction "13_13") (pintype "passive"))
      (node (ref "U$3") (pin "14") (pinfunction "14_14") (pintype "passive"))
    )
    (net (code "109") (name "OUT_23") (class "Default")
      (node (ref "IC10") (pin "1") (pinfunction "OUT_1") (pintype "output"))
      (node (ref "IC10") (pin "2") (pinfunction "-IN_2") (pintype "input"))
      (node (ref "U$3") (pin "15") (pinfunction "15_15") (pintype "passive"))
      (node (ref "U$3") (pin "16") (pinfunction "16_16") (pintype "passive"))
    )
    (net (code "110") (name "OUT_24") (class "Default")
      (node (ref "IC15") (pin "13") (pinfunction "-IN_13") (pintype "input"))
      (node (ref "IC15") (pin "14") (pinfunction "OUT_14") (pintype "output"))
      (node (ref "U$3") (pin "17") (pinfunction "17_17") (pintype "passive"))
      (node (ref "U$3") (pin "18") (pinfunction "18_18") (pintype "passive"))
    )
    (net (code "111") (name "OUT_25") (class "Default")
      (node (ref "IC15") (pin "8") (pinfunction "OUT_8") (pintype "output"))
      (node (ref "IC15") (pin "9") (pinfunction "-IN_9") (pintype "input"))
      (node (ref "U$3") (pin "19") (pinfunction "19_19") (pintype "passive"))
      (node (ref "U$3") (pin "20") (pinfunction "20_20") (pintype "passive"))
    )
    (net (code "112") (name "OUT_26") (class "Default")
      (node (ref "IC15") (pin "6") (pinfunction "-IN_6") (pintype "input"))
      (node (ref "IC15") (pin "7") (pinfunction "OUT_7") (pintype "output"))
      (node (ref "U$3") (pin "21") (pinfunction "21_21") (pintype "passive"))
      (node (ref "U$3") (pin "22") (pinfunction "22_22") (pintype "passive"))
    )
    (net (code "113") (name "OUT_27") (class "Default")
      (node (ref "IC15") (pin "1") (pinfunction "OUT_1") (pintype "output"))
      (node (ref "IC15") (pin "2") (pinfunction "-IN_2") (pintype "input"))
      (node (ref "U$3") (pin "23") (pinfunction "23_23") (pintype "passive"))
      (node (ref "U$3") (pin "24") (pinfunction "24_24") (pintype "passive"))
    )
    (net (code "114") (name "OUT_28") (class "Default")
      (node (ref "IC16") (pin "13") (pinfunction "-IN_13") (pintype "input"))
      (node (ref "IC16") (pin "14") (pinfunction "OUT_14") (pintype "output"))
      (node (ref "U$3") (pin "25") (pinfunction "25_25") (pintype "passive"))
      (node (ref "U$3") (pin "26") (pinfunction "26_26") (pintype "passive"))
    )
    (net (code "115") (name "OUT_29") (class "Default")
      (node (ref "IC16") (pin "8") (pinfunction "OUT_8") (pintype "output"))
      (node (ref "IC16") (pin "9") (pinfunction "-IN_9") (pintype "input"))
      (node (ref "U$3") (pin "27") (pinfunction "27_27") (pintype "passive"))
      (node (ref "U$3") (pin "28") (pinfunction "28_28") (pintype "passive"))
    )
    (net (code "116") (name "OUT_30") (class "Default")
      (node (ref "IC16") (pin "6") (pinfunction "-IN_6") (pintype "input"))
      (node (ref "IC16") (pin "7") (pinfunction "OUT_7") (pintype "output"))
      (node (ref "U$3") (pin "29") (pinfunction "29_29") (pintype "passive"))
      (node (ref "U$3") (pin "30") (pinfunction "30_30") (pintype "passive"))
    )
    (net (code "117") (name "OUT_31") (class "Default")
      (node (ref "IC16") (pin "1") (pinfunction "OUT_1") (pintype "output"))
      (node (ref "IC16") (pin "2") (pinfunction "-IN_2") (pintype "input"))
      (node (ref "X9") (pin "1") (pinfunction "1_1") (pintype "passive"))
    )
    (net (code "118") (name "OUT_32") (class "Default")
      (node (ref "IC21") (pin "13") (pinfunction "-IN_13") (pintype "input"))
      (node (ref "IC21") (pin "14") (pinfunction "OUT_14") (pintype "output"))
      (node (ref "X9") (pin "2") (pinfunction "2_2") (pintype "passive"))
    )
    (net (code "119") (name "OUT_33") (class "Default")
      (node (ref "IC21") (pin "8") (pinfunction "OUT_8") (pintype "output"))
      (node (ref "IC21") (pin "9") (pinfunction "-IN_9") (pintype "input"))
      (node (ref "X10") (pin "1") (pinfunction "1_1") (pintype "passive"))
      (node (ref "X10") (pin "2") (pinfunction "2_2") (pintype "passive"))
    )
    (net (code "120") (name "OUT_34") (class "Default")
      (node (ref "IC21") (pin "6") (pinfunction "-IN_6") (pintype "input"))
      (node (ref "IC21") (pin "7") (pinfunction "OUT_7") (pintype "output"))
      (node (ref "X10") (pin "3") (pinfunction "3_3") (pintype "passive"))
      (node (ref "X10") (pin "4") (pinfunction "4_4") (pintype "passive"))
    )
    (net (code "121") (name "OUT_35") (class "Default")
      (node (ref "IC21") (pin "1") (pinfunction "OUT_1") (pintype "output"))
      (node (ref "IC21") (pin "2") (pinfunction "-IN_2") (pintype "input"))
      (node (ref "X10") (pin "5") (pinfunction "5_5") (pintype "passive"))
      (node (ref "X10") (pin "6") (pinfunction "6_6") (pintype "passive"))
    )
    (net (code "122") (name "OUT_36") (class "Default")
      (node (ref "IC22") (pin "13") (pinfunction "-IN_13") (pintype "input"))
      (node (ref "IC22") (pin "14") (pinfunction "OUT_14") (pintype "output"))
      (node (ref "X10") (pin "7") (pinfunction "7_7") (pintype "passive"))
      (node (ref "X10") (pin "8") (pinfunction "8_8") (pintype "passive"))
    )
    (net (code "123") (name "OUT_37") (class "Default")
      (node (ref "IC22") (pin "8") (pinfunction "OUT_8") (pintype "output"))
      (node (ref "IC22") (pin "9") (pinfunction "-IN_9") (pintype "input"))
      (node (ref "X10") (pin "10") (pinfunction "10_10") (pintype "passive"))
      (node (ref "X10") (pin "9") (pinfunction "9_9") (pintype "passive"))
    )
    (net (code "124") (name "OUT_38") (class "Default")
      (node (ref "IC22") (pin "6") (pinfunction "-IN_6") (pintype "input"))
      (node (ref "IC22") (pin "7") (pinfunction "OUT_7") (pintype "output"))
      (node (ref "X10") (pin "11") (pinfunction "11_11") (pintype "passive"))
      (node (ref "X10") (pin "12") (pinfunction "12_12") (pintype "passive"))
    )
    (net (code "125") (name "OUT_39") (class "Default")
      (node (ref "IC22") (pin "1") (pinfunction "OUT_1") (pintype "output"))
      (node (ref "IC22") (pin "2") (pinfunction "-IN_2") (pintype "input"))
      (node (ref "X10") (pin "13") (pinfunction "13_13") (pintype "passive"))
      (node (ref "X10") (pin "14") (pinfunction "14_14") (pintype "passive"))
    )
    (net (code "126") (name "OUT_40") (class "Default")
      (node (ref "IC18") (pin "13") (pinfunction "-IN_13") (pintype "input"))
      (node (ref "IC18") (pin "14") (pinfunction "OUT_14") (pintype "output"))
      (node (ref "X4") (pin "1") (pinfunction "1_1") (pintype "passive"))
    )
    (net (code "127") (name "OUT_41") (class "Default")
      (node (ref "IC18") (pin "8") (pinfunction "OUT_8") (pintype "output"))
      (node (ref "IC18") (pin "9") (pinfunction "-IN_9") (pintype "input"))
      (node (ref "U$4") (pin "1") (pinfunction "1_1") (pintype "passive"))
      (node (ref "U$4") (pin "2") (pinfunction "2_2") (pintype "passive"))
    )
    (net (code "128") (name "OUT_42") (class "Default")
      (node (ref "IC18") (pin "6") (pinfunction "-IN_6") (pintype "input"))
      (node (ref "IC18") (pin "7") (pinfunction "OUT_7") (pintype "output"))
      (node (ref "U$4") (pin "3") (pinfunction "3_3") (pintype "passive"))
      (node (ref "U$4") (pin "4") (pinfunction "4_4") (pintype "passive"))
    )
    (net (code "129") (name "OUT_43") (class "Default")
      (node (ref "IC18") (pin "1") (pinfunction "OUT_1") (pintype "output"))
      (node (ref "IC18") (pin "2") (pinfunction "-IN_2") (pintype "input"))
      (node (ref "U$4") (pin "5") (pinfunction "5_5") (pintype "passive"))
      (node (ref "U$4") (pin "6") (pinfunction "6_6") (pintype "passive"))
    )
    (net (code "130") (name "OUT_44") (class "Default")
      (node (ref "IC19") (pin "13") (pinfunction "-IN_13") (pintype "input"))
      (node (ref "IC19") (pin "14") (pinfunction "OUT_14") (pintype "output"))
      (node (ref "U$4") (pin "7") (pinfunction "7_7") (pintype "passive"))
      (node (ref "U$4") (pin "8") (pinfunction "8_8") (pintype "passive"))
    )
    (net (code "131") (name "OUT_45") (class "Default")
      (node (ref "IC19") (pin "8") (pinfunction "OUT_8") (pintype "output"))
      (node (ref "IC19") (pin "9") (pinfunction "-IN_9") (pintype "input"))
      (node (ref "U$4") (pin "10") (pinfunction "10_10") (pintype "passive"))
      (node (ref "U$4") (pin "9") (pinfunction "9_9") (pintype "passive"))
    )
    (net (code "132") (name "OUT_46") (class "Default")
      (node (ref "IC19") (pin "6") (pinfunction "-IN_6") (pintype "input"))
      (node (ref "IC19") (pin "7") (pinfunction "OUT_7") (pintype "output"))
      (node (ref "U$4") (pin "11") (pinfunction "11_11") (pintype "passive"))
      (node (ref "U$4") (pin "12") (pinfunction "12_12") (pintype "passive"))
    )
    (net (code "133") (name "OUT_47") (class "Default")
      (node (ref "IC19") (pin "1") (pinfunction "OUT_1") (pintype "output"))
      (node (ref "IC19") (pin "2") (pinfunction "-IN_2") (pintype "input"))
      (node (ref "U$4") (pin "13") (pinfunction "13_13") (pintype "passive"))
      (node (ref "U$4") (pin "14") (pinfunction "14_14") (pintype "passive"))
    )
    (net (code "134") (name "OUT_48") (class "Default")
      (node (ref "IC27") (pin "13") (pinfunction "-IN_13") (pintype "input"))
      (node (ref "IC27") (pin "14") (pinfunction "OUT_14") (pintype "output"))
      (node (ref "U$4") (pin "15") (pinfunction "15_15") (pintype "passive"))
      (node (ref "U$4") (pin "16") (pinfunction "16_16") (pintype "passive"))
    )
    (net (code "135") (name "OUT_49") (class "Default")
      (node (ref "IC27") (pin "8") (pinfunction "OUT_8") (pintype "output"))
      (node (ref "IC27") (pin "9") (pinfunction "-IN_9") (pintype "input"))
      (node (ref "U$4") (pin "17") (pinfunction "17_17") (pintype "passive"))
      (node (ref "U$4") (pin "18") (pinfunction "18_18") (pintype "passive"))
    )
    (net (code "136") (name "OUT_50") (class "Default")
      (node (ref "IC27") (pin "6") (pinfunction "-IN_6") (pintype "input"))
      (node (ref "IC27") (pin "7") (pinfunction "OUT_7") (pintype "output"))
      (node (ref "U$4") (pin "19") (pinfunction "19_19") (pintype "passive"))
      (node (ref "U$4") (pin "20") (pinfunction "20_20") (pintype "passive"))
    )
    (net (code "137") (name "OUT_51") (class "Default")
      (node (ref "IC27") (pin "1") (pinfunction "OUT_1") (pintype "output"))
      (node (ref "IC27") (pin "2") (pinfunction "-IN_2") (pintype "input"))
      (node (ref "U$4") (pin "21") (pinfunction "21_21") (pintype "passive"))
      (node (ref "U$4") (pin "22") (pinfunction "22_22") (pintype "passive"))
    )
    (net (code "138") (name "OUT_52") (class "Default")
      (node (ref "IC28") (pin "13") (pinfunction "-IN_13") (pintype "input"))
      (node (ref "IC28") (pin "14") (pinfunction "OUT_14") (pintype "output"))
      (node (ref "U$4") (pin "23") (pinfunction "23_23") (pintype "passive"))
      (node (ref "U$4") (pin "24") (pinfunction "24_24") (pintype "passive"))
    )
    (net (code "139") (name "OUT_53") (class "Default")
      (node (ref "IC28") (pin "8") (pinfunction "OUT_8") (pintype "output"))
      (node (ref "IC28") (pin "9") (pinfunction "-IN_9") (pintype "input"))
      (node (ref "U$4") (pin "25") (pinfunction "25_25") (pintype "passive"))
      (node (ref "U$4") (pin "26") (pinfunction "26_26") (pintype "passive"))
    )
    (net (code "140") (name "OUT_54") (class "Default")
      (node (ref "IC28") (pin "6") (pinfunction "-IN_6") (pintype "input"))
      (node (ref "IC28") (pin "7") (pinfunction "OUT_7") (pintype "output"))
      (node (ref "U$4") (pin "27") (pinfunction "27_27") (pintype "passive"))
      (node (ref "U$4") (pin "28") (pinfunction "28_28") (pintype "passive"))
    )
    (net (code "141") (name "OUT_55") (class "Default")
      (node (ref "IC28") (pin "1") (pinfunction "OUT_1") (pintype "output"))
      (node (ref "IC28") (pin "2") (pinfunction "-IN_2") (pintype "input"))
      (node (ref "U$4") (pin "29") (pinfunction "29_29") (pintype "passive"))
      (node (ref "U$4") (pin "30") (pinfunction "30_30") (pintype "passive"))
    )
    (net (code "142") (name "SCK") (class "Default")
      (node (ref "IC2") (pin "10") (pinfunction "SCLK_10") (pintype "bidirectional"))
      (node (ref "X6") (pin "7") (pinfunction "7_7") (pintype "passive"))
    )
    (net (code "143") (name "SDA") (class "Default")
      (node (ref "IC2") (pin "11") (pinfunction "DIN_11") (pintype "bidirectional"))
      (node (ref "X6") (pin "8") (pinfunction "8_8") (pintype "passive"))
    )
    (net (code "144") (name "unconnected-(X6-Pad5)") (class "Default")
      (node (ref "X6") (pin "5") (pinfunction "5_5") (pintype "passive"))
    )
    (net (code "145") (name "unconnected-(X6-Pad12)") (class "Default")
      (node (ref "X6") (pin "12") (pinfunction "12_12") (pintype "passive"))
    )
    (net (code "146") (name "unconnected-(X6-Pad13)") (class "Default")
      (node (ref "X6") (pin "13") (pinfunction "13_13") (pintype "passive"))
    )
    (net (code "147") (name "~{SYNC}") (class "Default")
      (node (ref "IC2") (pin "9") (pinfunction "~{SYNC}_9") (pintype "bidirectional"))
      (node (ref "X6") (pin "10") (pinfunction "10_10") (pintype "passive"))
    )
  )
)
